# teensy-boom.net
KiCad netlist of a schematic drawn in EAGLE
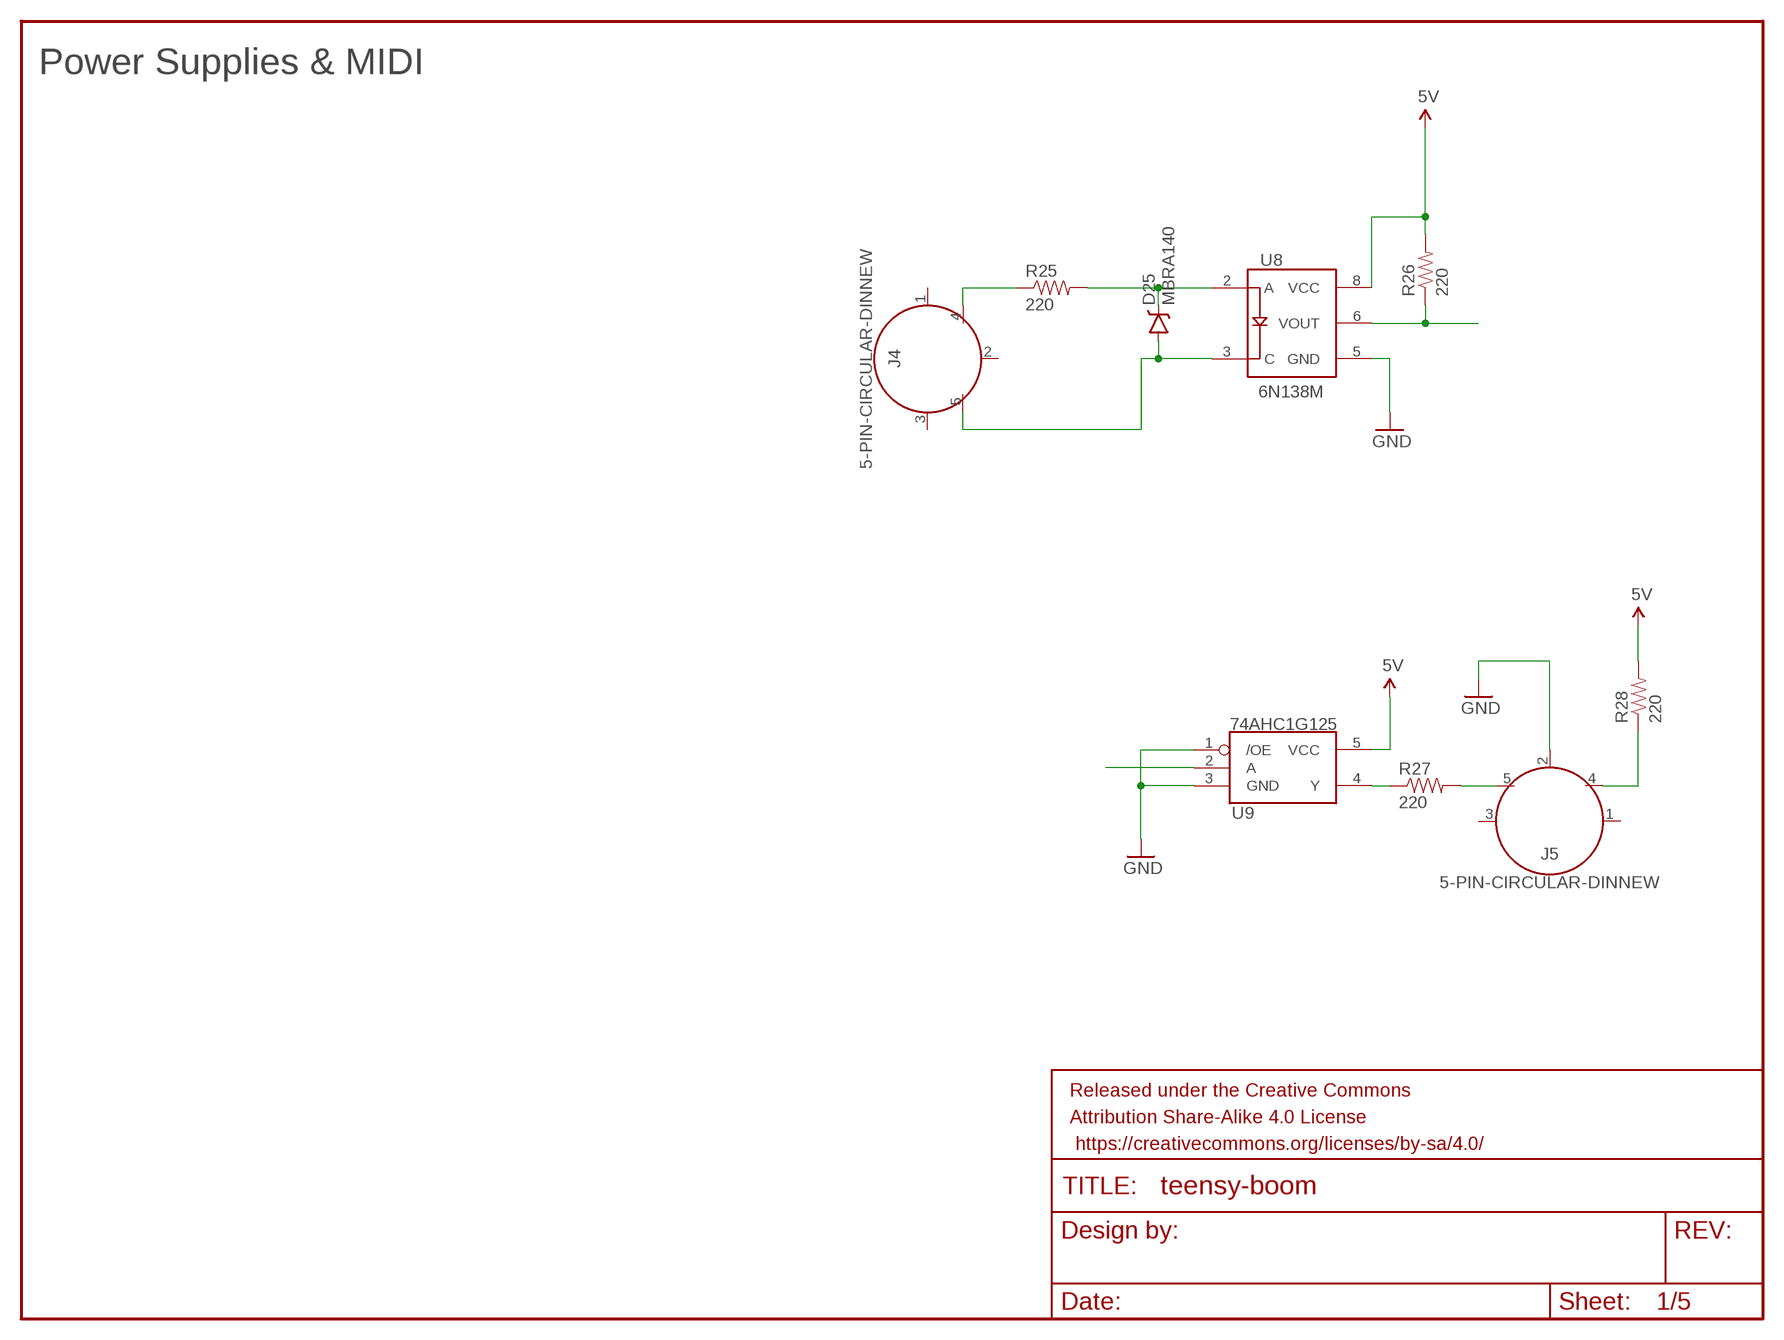
[diagram p0: schematic, sheet 1]
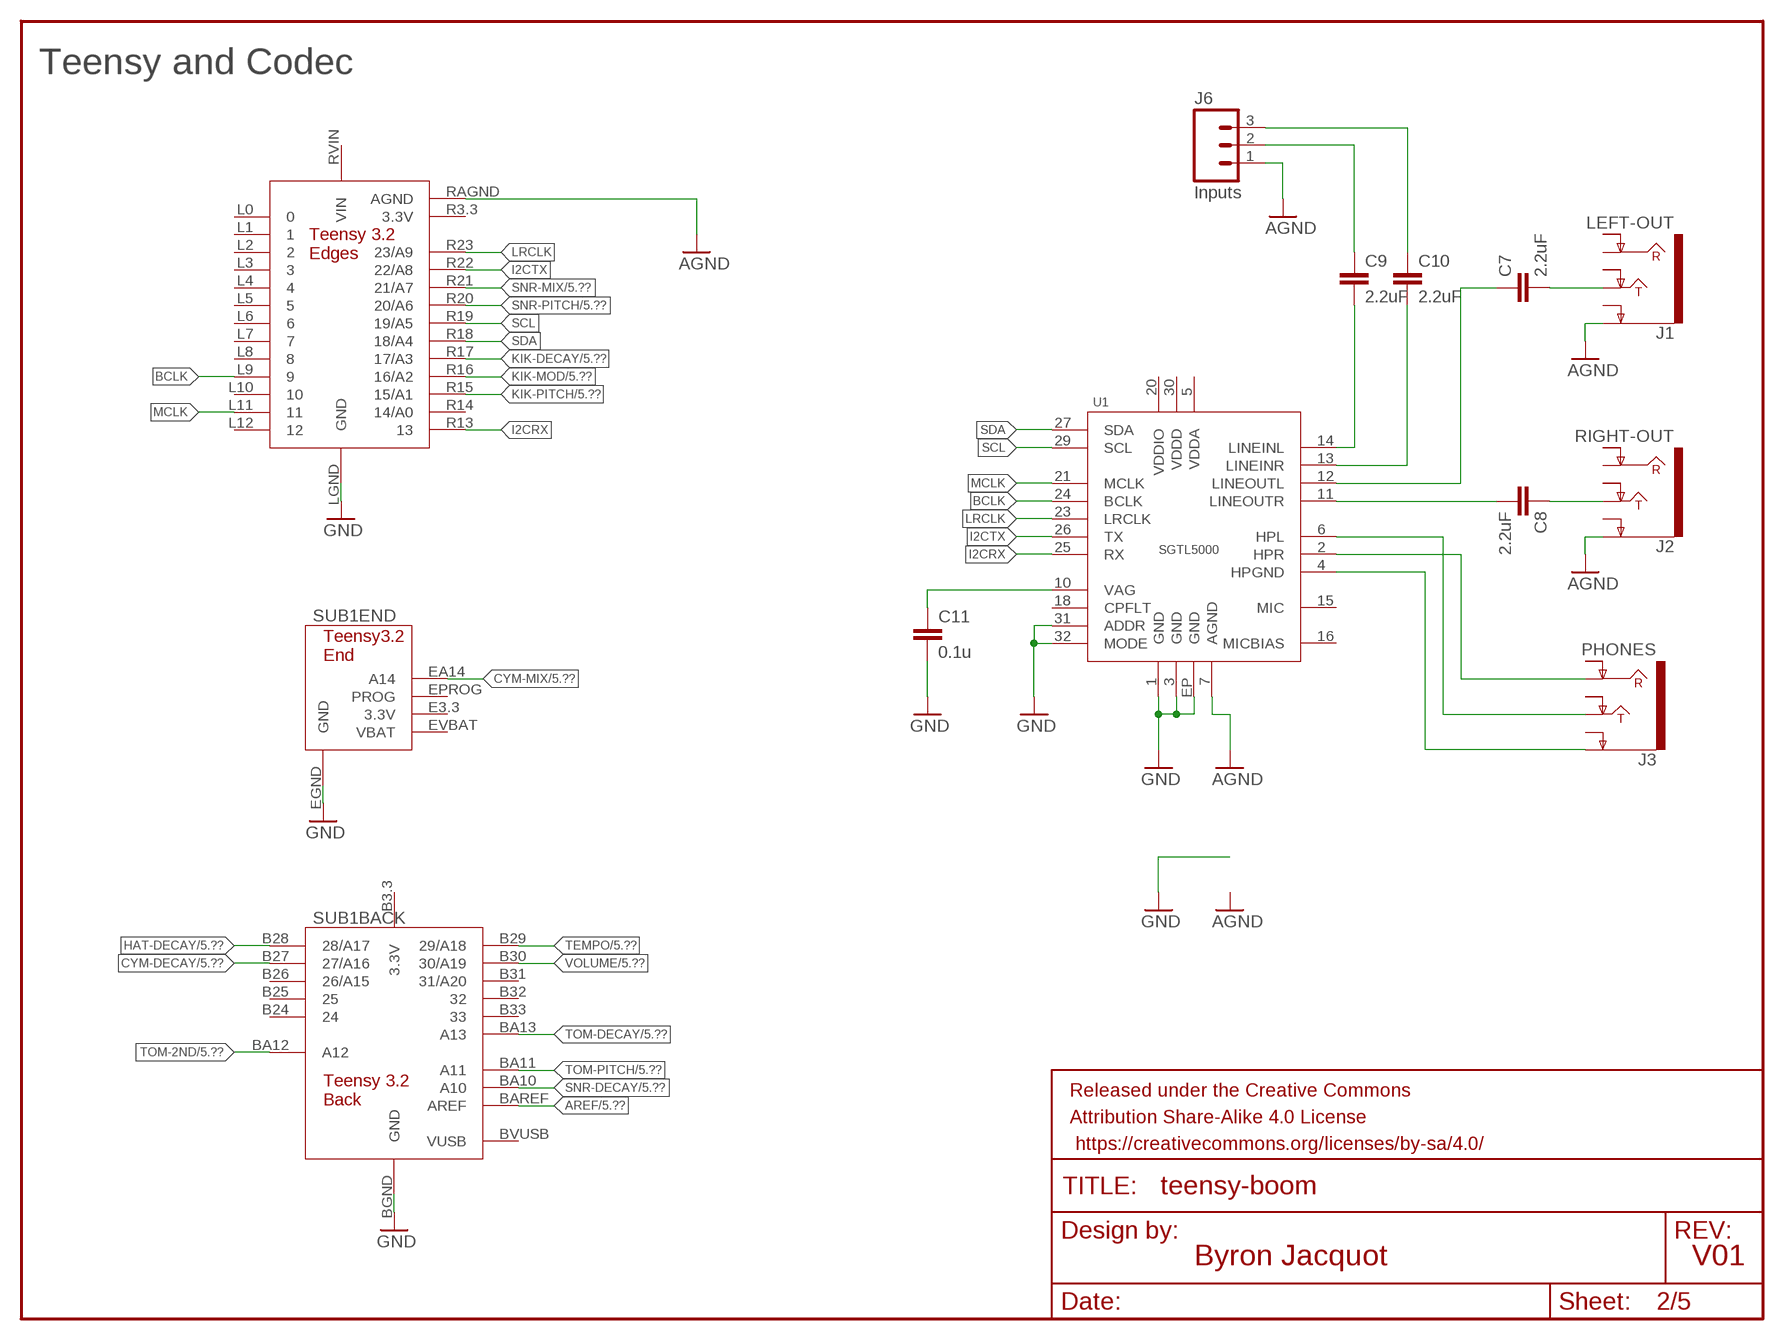
[diagram p1: schematic, sheet 2]
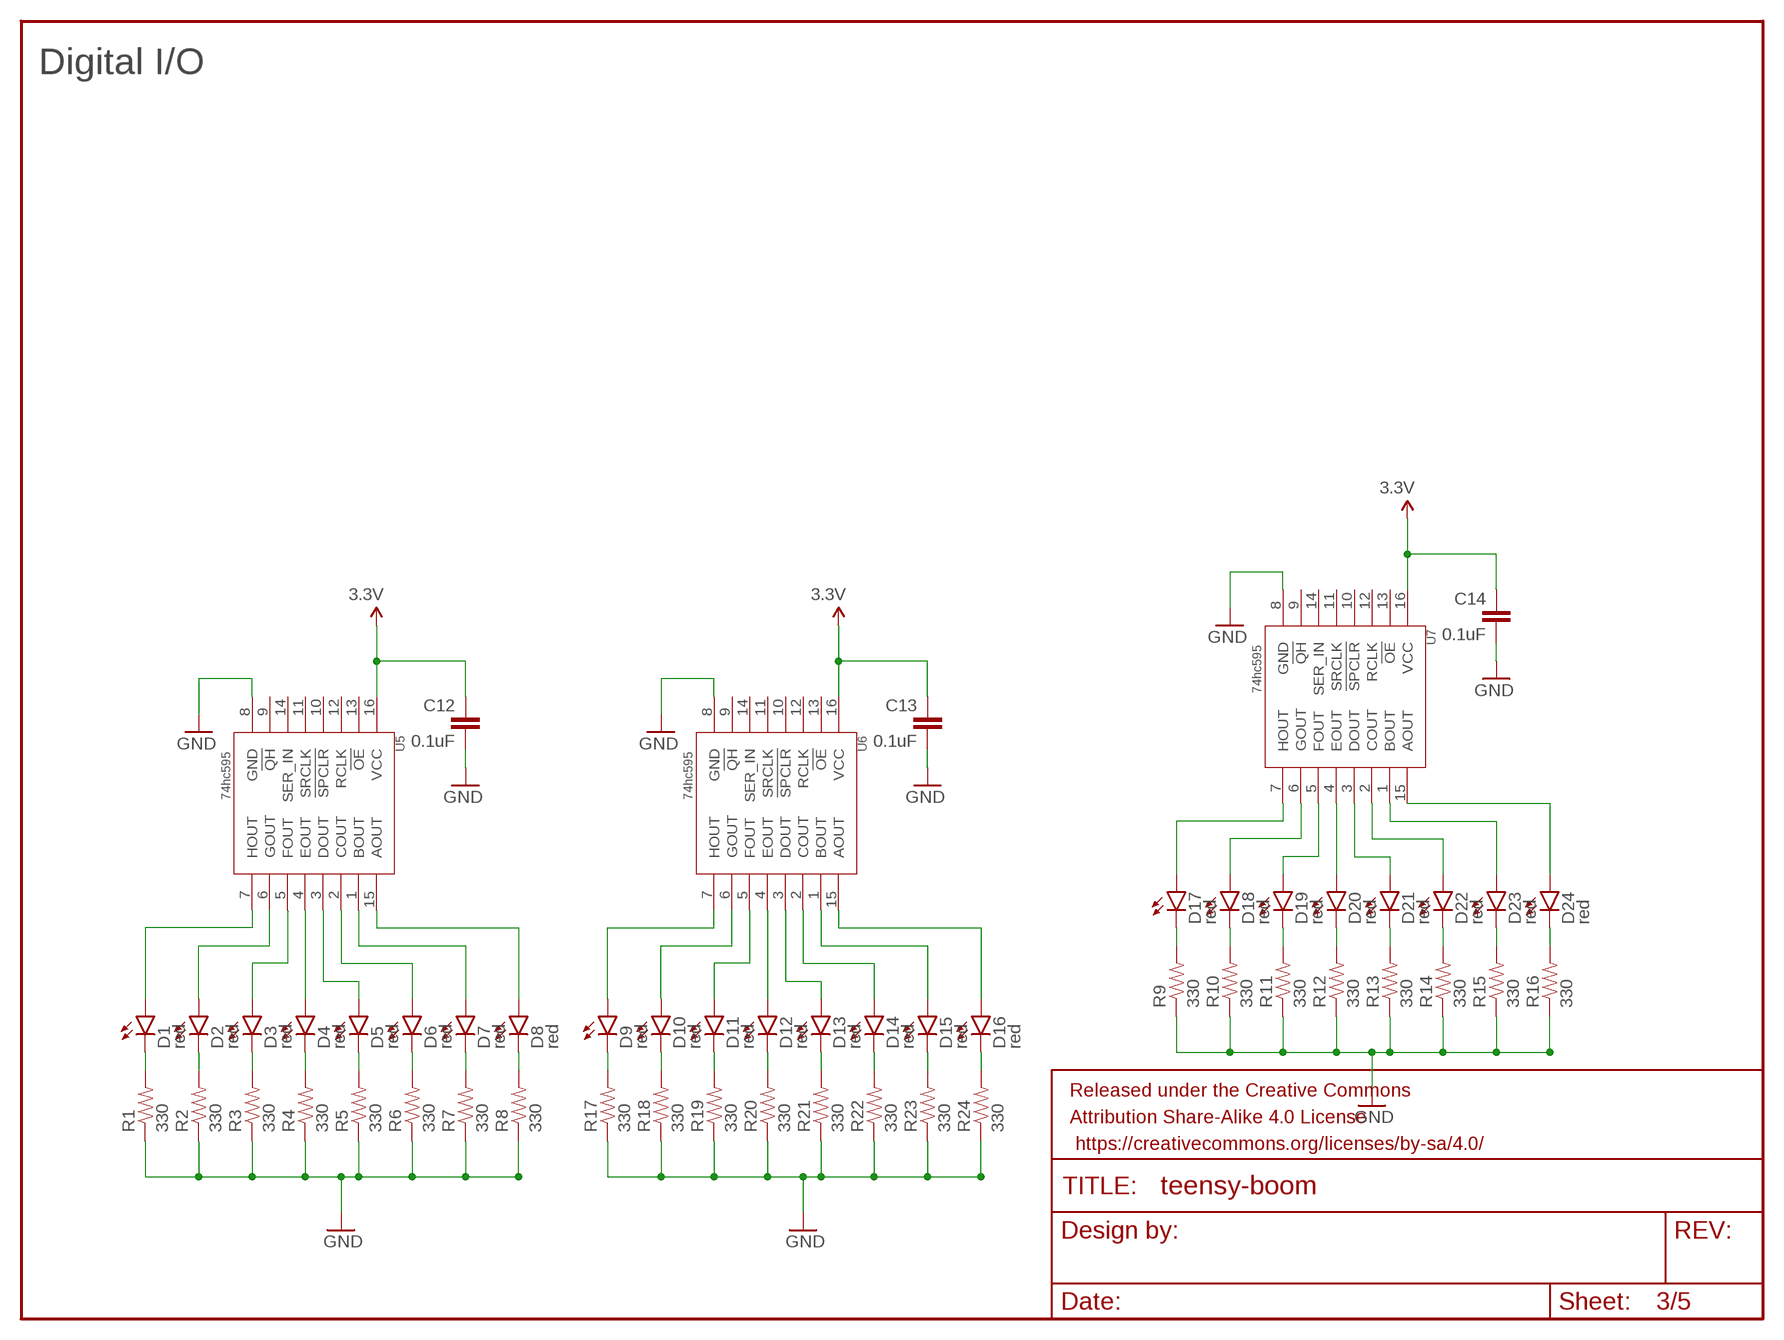
[diagram p2: schematic, sheet 3]
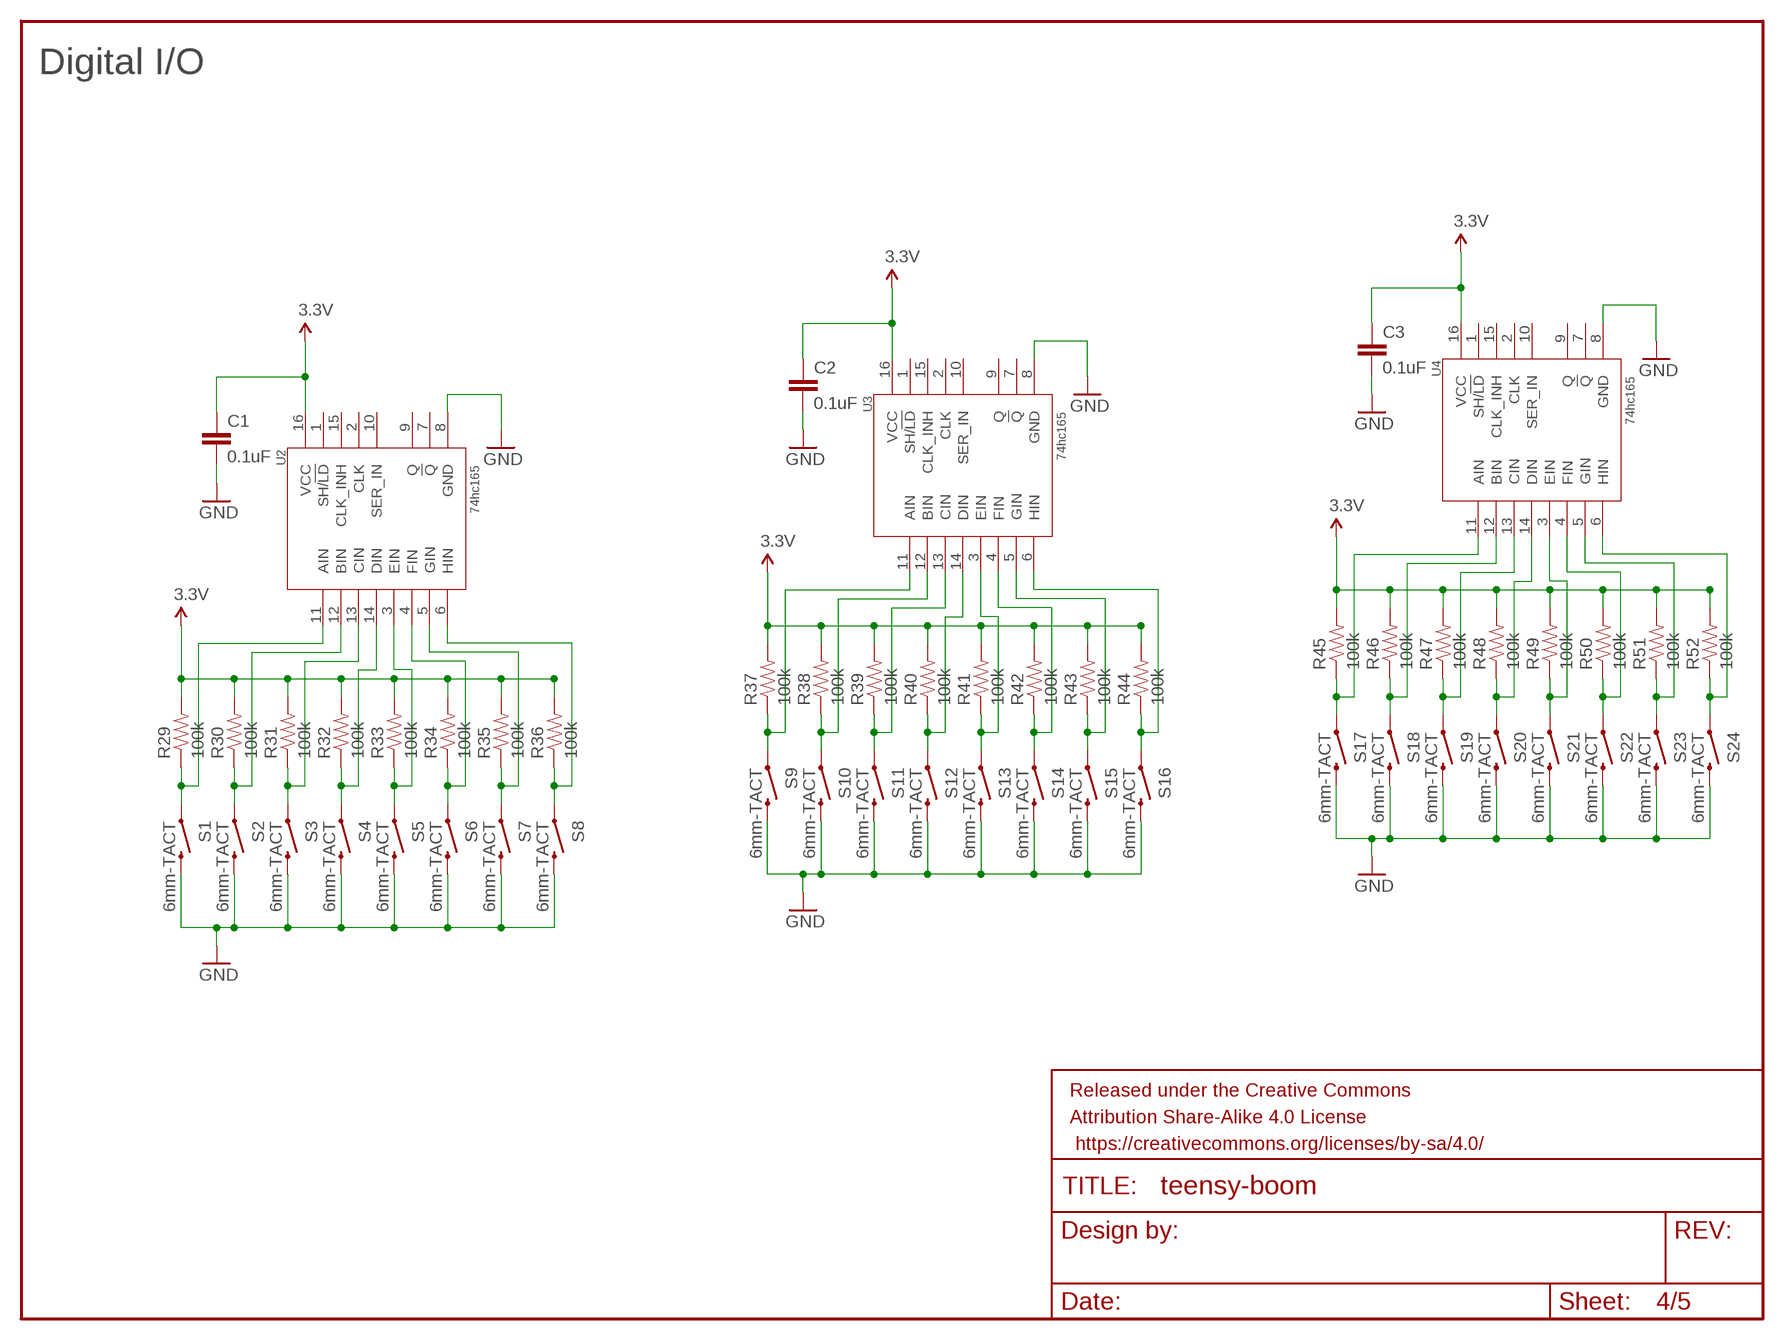
[diagram p3: schematic, sheet 4]
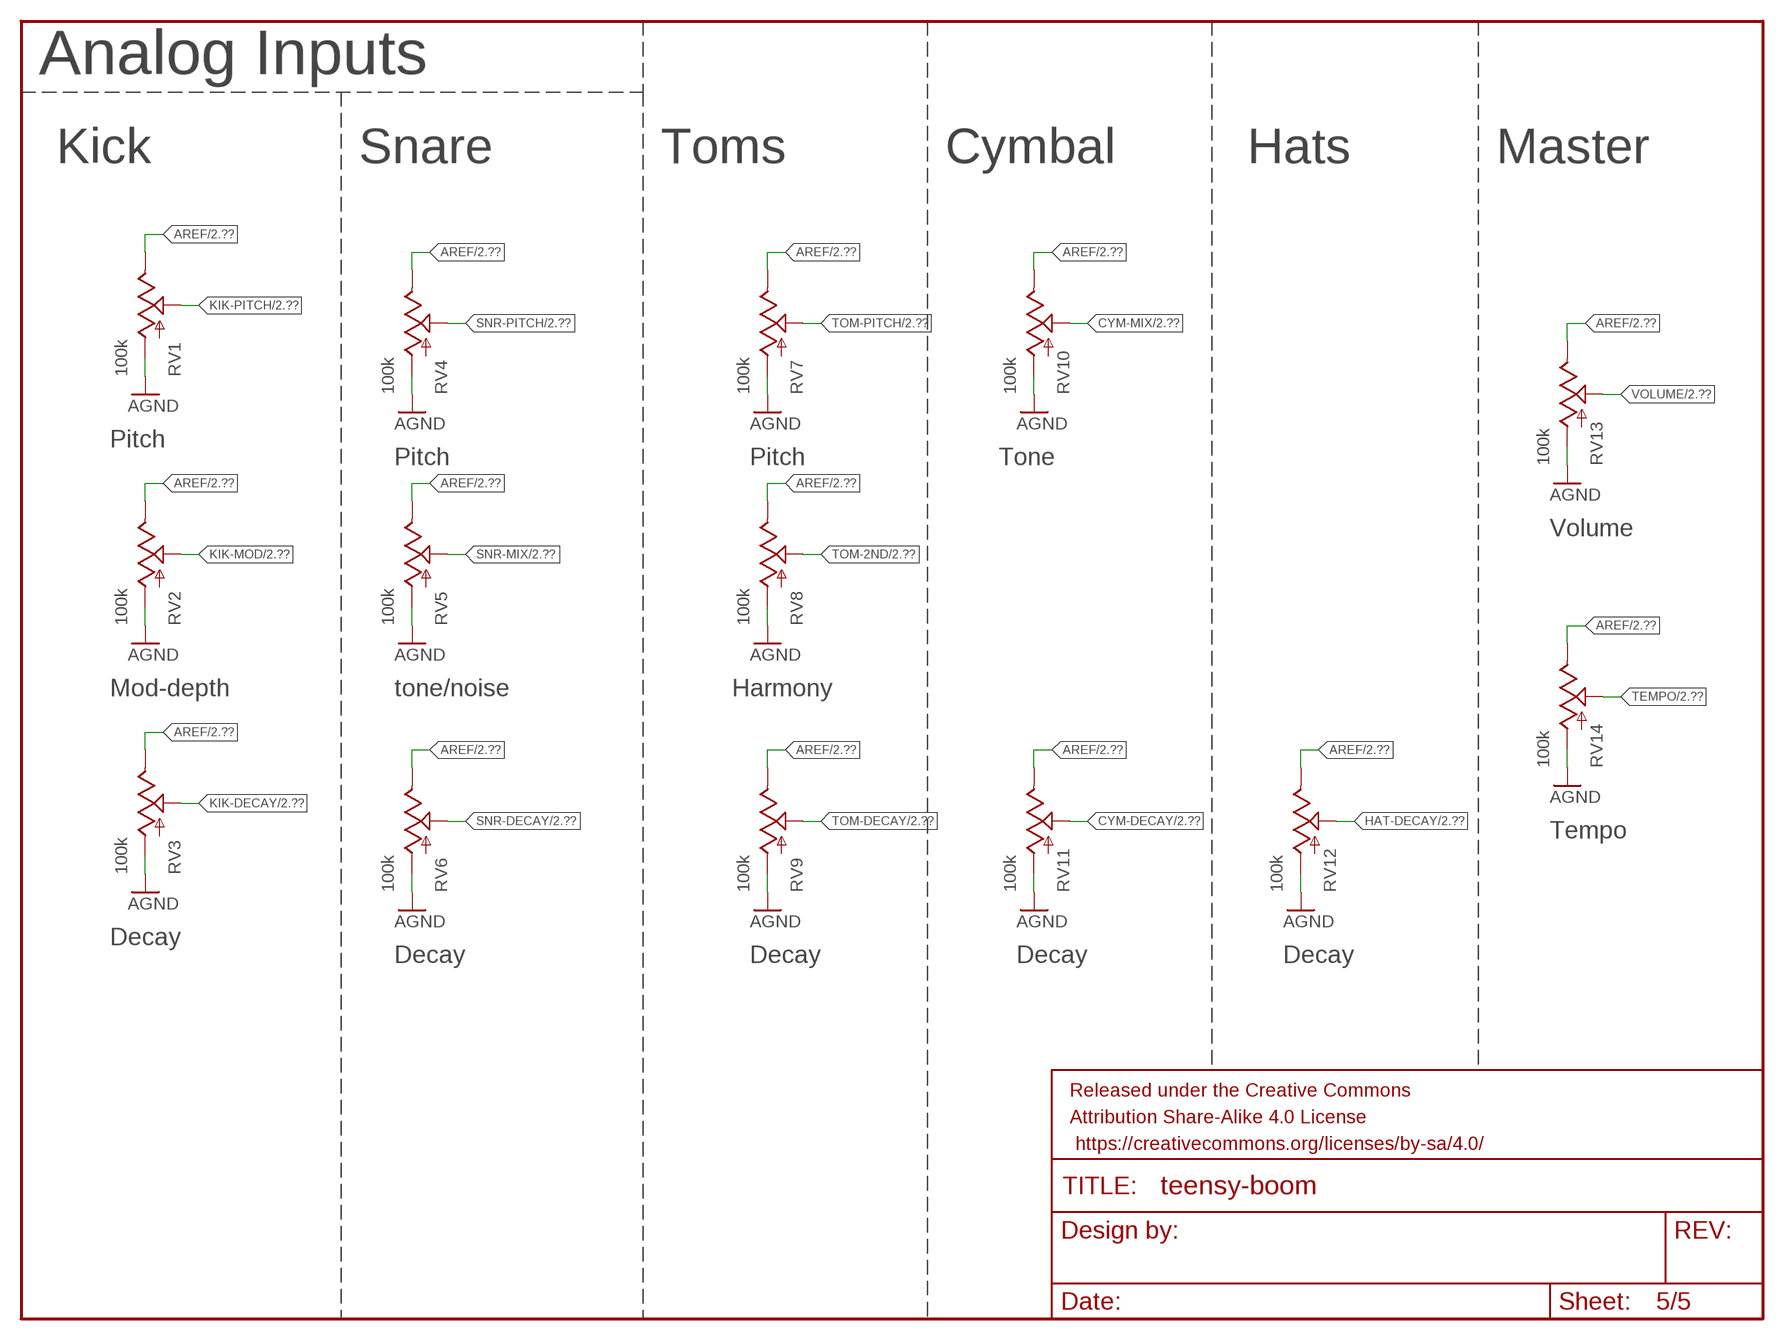
[diagram p4: schematic, sheet 5]

(export (version "E")
  (design (tool "Eeschema 10.0.6"))
  (components
    (comp (ref "C1")
      (value "0.1uF")
      (footprint "eagle-import:0603-CAP")
      (libsource (lib "eagle-import") (part "0.1UF-25V-5%(0603)"))
    )
    (comp (ref "C2")
      (value "0.1uF")
      (footprint "eagle-import:0603-CAP")
      (libsource (lib "eagle-import") (part "0.1UF-25V-5%(0603)"))
    )
    (comp (ref "C3")
      (value "0.1uF")
      (footprint "eagle-import:0603-CAP")
      (libsource (lib "eagle-import") (part "0.1UF-25V-5%(0603)"))
    )
    (comp (ref "FRAME5")
      (value "FRAME-LETTERNO_PACKAGE")
      (footprint "eagle-import:DUMMY")
      (fields (field (name "DESIGNER") "Nobody"))
      (libsource (lib "eagle-import") (part "FRAME-LETTERNO_PACKAGE"))
    )
    (comp (ref "R29")
      (value "100k")
      (footprint "eagle-import:0805")
      (libsource (lib "eagle-import") (part "RESISTOR0805-RES"))
    )
    (comp (ref "R30")
      (value "100k")
      (footprint "eagle-import:0805")
      (libsource (lib "eagle-import") (part "RESISTOR0805-RES"))
    )
    (comp (ref "R31")
      (value "100k")
      (footprint "eagle-import:0805")
      (libsource (lib "eagle-import") (part "RESISTOR0805-RES"))
    )
    (comp (ref "R32")
      (value "100k")
      (footprint "eagle-import:0805")
      (libsource (lib "eagle-import") (part "RESISTOR0805-RES"))
    )
    (comp (ref "R33")
      (value "100k")
      (footprint "eagle-import:0805")
      (libsource (lib "eagle-import") (part "RESISTOR0805-RES"))
    )
    (comp (ref "R34")
      (value "100k")
      (footprint "eagle-import:0805")
      (libsource (lib "eagle-import") (part "RESISTOR0805-RES"))
    )
    (comp (ref "R35")
      (value "100k")
      (footprint "eagle-import:0805")
      (libsource (lib "eagle-import") (part "RESISTOR0805-RES"))
    )
    (comp (ref "R36")
      (value "100k")
      (footprint "eagle-import:0805")
      (libsource (lib "eagle-import") (part "RESISTOR0805-RES"))
    )
    (comp (ref "R37")
      (value "100k")
      (footprint "eagle-import:0805")
      (libsource (lib "eagle-import") (part "RESISTOR0805-RES"))
    )
    (comp (ref "R38")
      (value "100k")
      (footprint "eagle-import:0805")
      (libsource (lib "eagle-import") (part "RESISTOR0805-RES"))
    )
    (comp (ref "R39")
      (value "100k")
      (footprint "eagle-import:0805")
      (libsource (lib "eagle-import") (part "RESISTOR0805-RES"))
    )
    (comp (ref "R40")
      (value "100k")
      (footprint "eagle-import:0805")
      (libsource (lib "eagle-import") (part "RESISTOR0805-RES"))
    )
    (comp (ref "R41")
      (value "100k")
      (footprint "eagle-import:0805")
      (libsource (lib "eagle-import") (part "RESISTOR0805-RES"))
    )
    (comp (ref "R42")
      (value "100k")
      (footprint "eagle-import:0805")
      (libsource (lib "eagle-import") (part "RESISTOR0805-RES"))
    )
    (comp (ref "R43")
      (value "100k")
      (footprint "eagle-import:0805")
      (libsource (lib "eagle-import") (part "RESISTOR0805-RES"))
    )
    (comp (ref "R44")
      (value "100k")
      (footprint "eagle-import:0805")
      (libsource (lib "eagle-import") (part "RESISTOR0805-RES"))
    )
    (comp (ref "R45")
      (value "100k")
      (footprint "eagle-import:0805")
      (libsource (lib "eagle-import") (part "RESISTOR0805-RES"))
    )
    (comp (ref "R46")
      (value "100k")
      (footprint "eagle-import:0805")
      (libsource (lib "eagle-import") (part "RESISTOR0805-RES"))
    )
    (comp (ref "R47")
      (value "100k")
      (footprint "eagle-import:0805")
      (libsource (lib "eagle-import") (part "RESISTOR0805-RES"))
    )
    (comp (ref "R48")
      (value "100k")
      (footprint "eagle-import:0805")
      (libsource (lib "eagle-import") (part "RESISTOR0805-RES"))
    )
    (comp (ref "R49")
      (value "100k")
      (footprint "eagle-import:0805")
      (libsource (lib "eagle-import") (part "RESISTOR0805-RES"))
    )
    (comp (ref "R50")
      (value "100k")
      (footprint "eagle-import:0805")
      (libsource (lib "eagle-import") (part "RESISTOR0805-RES"))
    )
    (comp (ref "R51")
      (value "100k")
      (footprint "eagle-import:0805")
      (libsource (lib "eagle-import") (part "RESISTOR0805-RES"))
    )
    (comp (ref "R52")
      (value "100k")
      (footprint "eagle-import:0805")
      (libsource (lib "eagle-import") (part "RESISTOR0805-RES"))
    )
    (comp (ref "S1")
      (value "6mm-TACT")
      (footprint "eagle-import:TACTILE-PTH")
      (libsource (lib "eagle-import") (part "SWITCH-MOMENTARY-2PTH"))
    )
    (comp (ref "S2")
      (value "6mm-TACT")
      (footprint "eagle-import:TACTILE-PTH")
      (libsource (lib "eagle-import") (part "SWITCH-MOMENTARY-2PTH"))
    )
    (comp (ref "S3")
      (value "6mm-TACT")
      (footprint "eagle-import:TACTILE-PTH")
      (libsource (lib "eagle-import") (part "SWITCH-MOMENTARY-2PTH"))
    )
    (comp (ref "S4")
      (value "6mm-TACT")
      (footprint "eagle-import:TACTILE-PTH")
      (libsource (lib "eagle-import") (part "SWITCH-MOMENTARY-2PTH"))
    )
    (comp (ref "S5")
      (value "6mm-TACT")
      (footprint "eagle-import:TACTILE-PTH")
      (libsource (lib "eagle-import") (part "SWITCH-MOMENTARY-2PTH"))
    )
    (comp (ref "S6")
      (value "6mm-TACT")
      (footprint "eagle-import:TACTILE-PTH")
      (libsource (lib "eagle-import") (part "SWITCH-MOMENTARY-2PTH"))
    )
    (comp (ref "S7")
      (value "6mm-TACT")
      (footprint "eagle-import:TACTILE-PTH")
      (libsource (lib "eagle-import") (part "SWITCH-MOMENTARY-2PTH"))
    )
    (comp (ref "S8")
      (value "6mm-TACT")
      (footprint "eagle-import:TACTILE-PTH")
      (libsource (lib "eagle-import") (part "SWITCH-MOMENTARY-2PTH"))
    )
    (comp (ref "S9")
      (value "6mm-TACT")
      (footprint "eagle-import:TACTILE-PTH")
      (libsource (lib "eagle-import") (part "SWITCH-MOMENTARY-2PTH"))
    )
    (comp (ref "S10")
      (value "6mm-TACT")
      (footprint "eagle-import:TACTILE-PTH")
      (libsource (lib "eagle-import") (part "SWITCH-MOMENTARY-2PTH"))
    )
    (comp (ref "S11")
      (value "6mm-TACT")
      (footprint "eagle-import:TACTILE-PTH")
      (libsource (lib "eagle-import") (part "SWITCH-MOMENTARY-2PTH"))
    )
    (comp (ref "S12")
      (value "6mm-TACT")
      (footprint "eagle-import:TACTILE-PTH")
      (libsource (lib "eagle-import") (part "SWITCH-MOMENTARY-2PTH"))
    )
    (comp (ref "S13")
      (value "6mm-TACT")
      (footprint "eagle-import:TACTILE-PTH")
      (libsource (lib "eagle-import") (part "SWITCH-MOMENTARY-2PTH"))
    )
    (comp (ref "S14")
      (value "6mm-TACT")
      (footprint "eagle-import:TACTILE-PTH")
      (libsource (lib "eagle-import") (part "SWITCH-MOMENTARY-2PTH"))
    )
    (comp (ref "S15")
      (value "6mm-TACT")
      (footprint "eagle-import:TACTILE-PTH")
      (libsource (lib "eagle-import") (part "SWITCH-MOMENTARY-2PTH"))
    )
    (comp (ref "S16")
      (value "6mm-TACT")
      (footprint "eagle-import:TACTILE-PTH")
      (libsource (lib "eagle-import") (part "SWITCH-MOMENTARY-2PTH"))
    )
    (comp (ref "S17")
      (value "6mm-TACT")
      (footprint "eagle-import:TACTILE-PTH")
      (libsource (lib "eagle-import") (part "SWITCH-MOMENTARY-2PTH"))
    )
    (comp (ref "S18")
      (value "6mm-TACT")
      (footprint "eagle-import:TACTILE-PTH")
      (libsource (lib "eagle-import") (part "SWITCH-MOMENTARY-2PTH"))
    )
    (comp (ref "S19")
      (value "6mm-TACT")
      (footprint "eagle-import:TACTILE-PTH")
      (libsource (lib "eagle-import") (part "SWITCH-MOMENTARY-2PTH"))
    )
    (comp (ref "S20")
      (value "6mm-TACT")
      (footprint "eagle-import:TACTILE-PTH")
      (libsource (lib "eagle-import") (part "SWITCH-MOMENTARY-2PTH"))
    )
    (comp (ref "S21")
      (value "6mm-TACT")
      (footprint "eagle-import:TACTILE-PTH")
      (libsource (lib "eagle-import") (part "SWITCH-MOMENTARY-2PTH"))
    )
    (comp (ref "S22")
      (value "6mm-TACT")
      (footprint "eagle-import:TACTILE-PTH")
      (libsource (lib "eagle-import") (part "SWITCH-MOMENTARY-2PTH"))
    )
    (comp (ref "S23")
      (value "6mm-TACT")
      (footprint "eagle-import:TACTILE-PTH")
      (libsource (lib "eagle-import") (part "SWITCH-MOMENTARY-2PTH"))
    )
    (comp (ref "S24")
      (value "6mm-TACT")
      (footprint "eagle-import:TACTILE-PTH")
      (libsource (lib "eagle-import") (part "SWITCH-MOMENTARY-2PTH"))
    )
    (comp (ref "U2")
      (value "74hc165")
      (footprint "eagle-import:SO16")
      (libsource (lib "eagle-import") (part "74HC165"))
    )
    (comp (ref "U3")
      (value "74hc165")
      (footprint "eagle-import:SO16")
      (libsource (lib "eagle-import") (part "74HC165"))
    )
    (comp (ref "U4")
      (value "74hc165")
      (footprint "eagle-import:SO16")
      (libsource (lib "eagle-import") (part "74HC165"))
    )
    (comp (ref "C7")
      (value "2.2uF")
      (footprint "eagle-import:0805-CAP")
      (libsource (lib "eagle-import") (part "2.2UF-25V-+80/-20(0805)"))
    )
    (comp (ref "C8")
      (value "2.2uF")
      (footprint "eagle-import:0805-CAP")
      (libsource (lib "eagle-import") (part "2.2UF-25V-+80/-20(0805)"))
    )
    (comp (ref "C9")
      (value "2.2uF")
      (footprint "eagle-import:0805-CAP")
      (libsource (lib "eagle-import") (part "2.2UF-25V-+80/-20(0805)"))
    )
    (comp (ref "C10")
      (value "2.2uF")
      (footprint "eagle-import:0805-CAP")
      (libsource (lib "eagle-import") (part "2.2UF-25V-+80/-20(0805)"))
    )
    (comp (ref "C11")
      (value "0.1u")
      (footprint "eagle-import:0805")
      (libsource (lib "eagle-import") (part "CAP0805"))
    )
    (comp (ref "FRAME1")
      (value "FRAME-LETTER")
      (footprint "eagle-import:CREATIVE_COMMONS")
      (libsource (lib "eagle-import") (part "FRAME-LETTER"))
    )
    (comp (ref "J1")
      (value "LEFT-OUT")
      (footprint "eagle-import:AUDIO-JACK-.25-INCH-HORIZ-PTH")
      (libsource (lib "eagle-import") (part "AUDIO-JACK4-.25-HORIZ-TRS"))
    )
    (comp (ref "J2")
      (value "RIGHT-OUT")
      (footprint "eagle-import:AUDIO-JACK-.25-INCH-HORIZ-PTH")
      (libsource (lib "eagle-import") (part "AUDIO-JACK4-.25-HORIZ-TRS"))
    )
    (comp (ref "J3")
      (value "PHONES")
      (footprint "eagle-import:AUDIO-JACK-.25-INCH-HORIZ-PTH")
      (libsource (lib "eagle-import") (part "AUDIO-JACK4-.25-HORIZ-TRS"))
    )
    (comp (ref "J6")
      (value "Inputs")
      (footprint "eagle-import:1X03_LOCK")
      (libsource (lib "eagle-import") (part "M03LOCK"))
    )
    (comp (ref "SUB1")
      (value "TEENSY-3.2PTH")
      (footprint "eagle-import:TEENSY-3.2")
      (libsource (lib "eagle-import") (part "TEENSY-3.2PTH"))
    )
    (comp (ref "U1")
      (value "SGTL5000")
      (footprint "eagle-import:QFN-32")
      (libsource (lib "eagle-import") (part "SGTL5000QFN-32"))
    )
    (comp (ref "FRAME4")
      (value "FRAME-LETTERNO_PACKAGE")
      (footprint "eagle-import:DUMMY")
      (fields (field (name "DESIGNER") "Nobody"))
      (libsource (lib "eagle-import") (part "FRAME-LETTERNO_PACKAGE"))
    )
    (comp (ref "RV1")
      (value "100k")
      (footprint "eagle-import:ALPS_POT_KIT")
      (libsource (lib "eagle-import") (part "POTALPS-KIT"))
    )
    (comp (ref "RV2")
      (value "100k")
      (footprint "eagle-import:ALPS_POT_KIT")
      (libsource (lib "eagle-import") (part "POTALPS-KIT"))
    )
    (comp (ref "RV3")
      (value "100k")
      (footprint "eagle-import:ALPS_POT_KIT")
      (libsource (lib "eagle-import") (part "POTALPS-KIT"))
    )
    (comp (ref "RV4")
      (value "100k")
      (footprint "eagle-import:ALPS_POT_KIT")
      (libsource (lib "eagle-import") (part "POTALPS-KIT"))
    )
    (comp (ref "RV5")
      (value "100k")
      (footprint "eagle-import:ALPS_POT_KIT")
      (libsource (lib "eagle-import") (part "POTALPS-KIT"))
    )
    (comp (ref "RV6")
      (value "100k")
      (footprint "eagle-import:ALPS_POT_KIT")
      (libsource (lib "eagle-import") (part "POTALPS-KIT"))
    )
    (comp (ref "RV7")
      (value "100k")
      (footprint "eagle-import:ALPS_POT_KIT")
      (libsource (lib "eagle-import") (part "POTALPS-KIT"))
    )
    (comp (ref "RV8")
      (value "100k")
      (footprint "eagle-import:ALPS_POT_KIT")
      (libsource (lib "eagle-import") (part "POTALPS-KIT"))
    )
    (comp (ref "RV9")
      (value "100k")
      (footprint "eagle-import:ALPS_POT_KIT")
      (libsource (lib "eagle-import") (part "POTALPS-KIT"))
    )
    (comp (ref "RV10")
      (value "100k")
      (footprint "eagle-import:ALPS_POT_KIT")
      (libsource (lib "eagle-import") (part "POTALPS-KIT"))
    )
    (comp (ref "RV11")
      (value "100k")
      (footprint "eagle-import:ALPS_POT_KIT")
      (libsource (lib "eagle-import") (part "POTALPS-KIT"))
    )
    (comp (ref "RV12")
      (value "100k")
      (footprint "eagle-import:ALPS_POT_KIT")
      (libsource (lib "eagle-import") (part "POTALPS-KIT"))
    )
    (comp (ref "RV13")
      (value "100k")
      (footprint "eagle-import:ALPS_POT_KIT")
      (libsource (lib "eagle-import") (part "POTALPS-KIT"))
    )
    (comp (ref "RV14")
      (value "100k")
      (footprint "eagle-import:ALPS_POT_KIT")
      (libsource (lib "eagle-import") (part "POTALPS-KIT"))
    )
    (comp (ref "C12")
      (value "0.1uF")
      (footprint "eagle-import:0603-CAP")
      (libsource (lib "eagle-import") (part "0.1UF-25V-5%(0603)"))
    )
    (comp (ref "C13")
      (value "0.1uF")
      (footprint "eagle-import:0603-CAP")
      (libsource (lib "eagle-import") (part "0.1UF-25V-5%(0603)"))
    )
    (comp (ref "C14")
      (value "0.1uF")
      (footprint "eagle-import:0603-CAP")
      (libsource (lib "eagle-import") (part "0.1UF-25V-5%(0603)"))
    )
    (comp (ref "D1")
      (value "red")
      (footprint "eagle-import:LED3MM-NS")
      (libsource (lib "eagle-import") (part "LED-3MM-NO_SILK"))
    )
    (comp (ref "D2")
      (value "red")
      (footprint "eagle-import:LED3MM-NS")
      (libsource (lib "eagle-import") (part "LED-3MM-NO_SILK"))
    )
    (comp (ref "D3")
      (value "red")
      (footprint "eagle-import:LED3MM-NS")
      (libsource (lib "eagle-import") (part "LED-3MM-NO_SILK"))
    )
    (comp (ref "D4")
      (value "red")
      (footprint "eagle-import:LED3MM-NS")
      (libsource (lib "eagle-import") (part "LED-3MM-NO_SILK"))
    )
    (comp (ref "D5")
      (value "red")
      (footprint "eagle-import:LED3MM-NS")
      (libsource (lib "eagle-import") (part "LED-3MM-NO_SILK"))
    )
    (comp (ref "D6")
      (value "red")
      (footprint "eagle-import:LED3MM-NS")
      (libsource (lib "eagle-import") (part "LED-3MM-NO_SILK"))
    )
    (comp (ref "D7")
      (value "red")
      (footprint "eagle-import:LED3MM-NS")
      (libsource (lib "eagle-import") (part "LED-3MM-NO_SILK"))
    )
    (comp (ref "D8")
      (value "red")
      (footprint "eagle-import:LED3MM-NS")
      (libsource (lib "eagle-import") (part "LED-3MM-NO_SILK"))
    )
    (comp (ref "D9")
      (value "red")
      (footprint "eagle-import:LED3MM-NS")
      (libsource (lib "eagle-import") (part "LED-3MM-NO_SILK"))
    )
    (comp (ref "D10")
      (value "red")
      (footprint "eagle-import:LED3MM-NS")
      (libsource (lib "eagle-import") (part "LED-3MM-NO_SILK"))
    )
    (comp (ref "D11")
      (value "red")
      (footprint "eagle-import:LED3MM-NS")
      (libsource (lib "eagle-import") (part "LED-3MM-NO_SILK"))
    )
    (comp (ref "D12")
      (value "red")
      (footprint "eagle-import:LED3MM-NS")
      (libsource (lib "eagle-import") (part "LED-3MM-NO_SILK"))
    )
    (comp (ref "D13")
      (value "red")
      (footprint "eagle-import:LED3MM-NS")
      (libsource (lib "eagle-import") (part "LED-3MM-NO_SILK"))
    )
    (comp (ref "D14")
      (value "red")
      (footprint "eagle-import:LED3MM-NS")
      (libsource (lib "eagle-import") (part "LED-3MM-NO_SILK"))
    )
    (comp (ref "D15")
      (value "red")
      (footprint "eagle-import:LED3MM-NS")
      (libsource (lib "eagle-import") (part "LED-3MM-NO_SILK"))
    )
    (comp (ref "D16")
      (value "red")
      (footprint "eagle-import:LED3MM-NS")
      (libsource (lib "eagle-import") (part "LED-3MM-NO_SILK"))
    )
    (comp (ref "D17")
      (value "red")
      (footprint "eagle-import:LED3MM-NS")
      (libsource (lib "eagle-import") (part "LED-3MM-NO_SILK"))
    )
    (comp (ref "D18")
      (value "red")
      (footprint "eagle-import:LED3MM-NS")
      (libsource (lib "eagle-import") (part "LED-3MM-NO_SILK"))
    )
    (comp (ref "D19")
      (value "red")
      (footprint "eagle-import:LED3MM-NS")
      (libsource (lib "eagle-import") (part "LED-3MM-NO_SILK"))
    )
    (comp (ref "D20")
      (value "red")
      (footprint "eagle-import:LED3MM-NS")
      (libsource (lib "eagle-import") (part "LED-3MM-NO_SILK"))
    )
    (comp (ref "D21")
      (value "red")
      (footprint "eagle-import:LED3MM-NS")
      (libsource (lib "eagle-import") (part "LED-3MM-NO_SILK"))
    )
    (comp (ref "D22")
      (value "red")
      (footprint "eagle-import:LED3MM-NS")
      (libsource (lib "eagle-import") (part "LED-3MM-NO_SILK"))
    )
    (comp (ref "D23")
      (value "red")
      (footprint "eagle-import:LED3MM-NS")
      (libsource (lib "eagle-import") (part "LED-3MM-NO_SILK"))
    )
    (comp (ref "D24")
      (value "red")
      (footprint "eagle-import:LED3MM-NS")
      (libsource (lib "eagle-import") (part "LED-3MM-NO_SILK"))
    )
    (comp (ref "FRAME3")
      (value "FRAME-LETTERNO_PACKAGE")
      (footprint "eagle-import:DUMMY")
      (fields (field (name "DESIGNER") "Nobody"))
      (libsource (lib "eagle-import") (part "FRAME-LETTERNO_PACKAGE"))
    )
    (comp (ref "R1")
      (value "330")
      (footprint "eagle-import:0603-RES")
      (libsource (lib "eagle-import") (part "330OHM1/10W1%(0603)"))
    )
    (comp (ref "R2")
      (value "330")
      (footprint "eagle-import:0603-RES")
      (libsource (lib "eagle-import") (part "330OHM1/10W1%(0603)"))
    )
    (comp (ref "R3")
      (value "330")
      (footprint "eagle-import:0603-RES")
      (libsource (lib "eagle-import") (part "330OHM1/10W1%(0603)"))
    )
    (comp (ref "R4")
      (value "330")
      (footprint "eagle-import:0603-RES")
      (libsource (lib "eagle-import") (part "330OHM1/10W1%(0603)"))
    )
    (comp (ref "R5")
      (value "330")
      (footprint "eagle-import:0603-RES")
      (libsource (lib "eagle-import") (part "330OHM1/10W1%(0603)"))
    )
    (comp (ref "R6")
      (value "330")
      (footprint "eagle-import:0603-RES")
      (libsource (lib "eagle-import") (part "330OHM1/10W1%(0603)"))
    )
    (comp (ref "R7")
      (value "330")
      (footprint "eagle-import:0603-RES")
      (libsource (lib "eagle-import") (part "330OHM1/10W1%(0603)"))
    )
    (comp (ref "R8")
      (value "330")
      (footprint "eagle-import:0603-RES")
      (libsource (lib "eagle-import") (part "330OHM1/10W1%(0603)"))
    )
    (comp (ref "R9")
      (value "330")
      (footprint "eagle-import:0603-RES")
      (libsource (lib "eagle-import") (part "330OHM1/10W1%(0603)"))
    )
    (comp (ref "R10")
      (value "330")
      (footprint "eagle-import:0603-RES")
      (libsource (lib "eagle-import") (part "330OHM1/10W1%(0603)"))
    )
    (comp (ref "R11")
      (value "330")
      (footprint "eagle-import:0603-RES")
      (libsource (lib "eagle-import") (part "330OHM1/10W1%(0603)"))
    )
    (comp (ref "R12")
      (value "330")
      (footprint "eagle-import:0603-RES")
      (libsource (lib "eagle-import") (part "330OHM1/10W1%(0603)"))
    )
    (comp (ref "R13")
      (value "330")
      (footprint "eagle-import:0603-RES")
      (libsource (lib "eagle-import") (part "330OHM1/10W1%(0603)"))
    )
    (comp (ref "R14")
      (value "330")
      (footprint "eagle-import:0603-RES")
      (libsource (lib "eagle-import") (part "330OHM1/10W1%(0603)"))
    )
    (comp (ref "R15")
      (value "330")
      (footprint "eagle-import:0603-RES")
      (libsource (lib "eagle-import") (part "330OHM1/10W1%(0603)"))
    )
    (comp (ref "R16")
      (value "330")
      (footprint "eagle-import:0603-RES")
      (libsource (lib "eagle-import") (part "330OHM1/10W1%(0603)"))
    )
    (comp (ref "R17")
      (value "330")
      (footprint "eagle-import:0603-RES")
      (libsource (lib "eagle-import") (part "330OHM1/10W1%(0603)"))
    )
    (comp (ref "R18")
      (value "330")
      (footprint "eagle-import:0603-RES")
      (libsource (lib "eagle-import") (part "330OHM1/10W1%(0603)"))
    )
    (comp (ref "R19")
      (value "330")
      (footprint "eagle-import:0603-RES")
      (libsource (lib "eagle-import") (part "330OHM1/10W1%(0603)"))
    )
    (comp (ref "R20")
      (value "330")
      (footprint "eagle-import:0603-RES")
      (libsource (lib "eagle-import") (part "330OHM1/10W1%(0603)"))
    )
    (comp (ref "R21")
      (value "330")
      (footprint "eagle-import:0603-RES")
      (libsource (lib "eagle-import") (part "330OHM1/10W1%(0603)"))
    )
    (comp (ref "R22")
      (value "330")
      (footprint "eagle-import:0603-RES")
      (libsource (lib "eagle-import") (part "330OHM1/10W1%(0603)"))
    )
    (comp (ref "R23")
      (value "330")
      (footprint "eagle-import:0603-RES")
      (libsource (lib "eagle-import") (part "330OHM1/10W1%(0603)"))
    )
    (comp (ref "R24")
      (value "330")
      (footprint "eagle-import:0603-RES")
      (libsource (lib "eagle-import") (part "330OHM1/10W1%(0603)"))
    )
    (comp (ref "U5")
      (value "74hc595")
      (footprint "eagle-import:SO16")
      (libsource (lib "eagle-import") (part "74HC595"))
    )
    (comp (ref "U6")
      (value "74hc595")
      (footprint "eagle-import:SO16")
      (libsource (lib "eagle-import") (part "74HC595"))
    )
    (comp (ref "U7")
      (value "74hc595")
      (footprint "eagle-import:SO16")
      (libsource (lib "eagle-import") (part "74HC595"))
    )
    (comp (ref "D25")
      (value "MBRA140")
      (footprint "eagle-import:SMA-DIODE")
      (libsource (lib "eagle-import") (part "DIODE-SCHOTTKY-MBRA140"))
    )
    (comp (ref "FRAME2")
      (value "FRAME-LETTERNO_PACKAGE")
      (footprint "eagle-import:DUMMY")
      (fields (field (name "DESIGNER") "Nobody"))
      (libsource (lib "eagle-import") (part "FRAME-LETTERNO_PACKAGE"))
    )
    (comp (ref "J4")
      (value "5-PIN-CIRCULAR-DINNEW")
      (footprint "eagle-import:5-PIN-DIN-RA-PCB-NEW")
      (libsource (lib "eagle-import") (part "5-PIN-CIRCULAR-DINNEW"))
    )
    (comp (ref "J5")
      (value "5-PIN-CIRCULAR-DINNEW")
      (footprint "eagle-import:5-PIN-DIN-RA-PCB-NEW")
      (libsource (lib "eagle-import") (part "5-PIN-CIRCULAR-DINNEW"))
    )
    (comp (ref "R25")
      (value "220")
      (footprint "eagle-import:0603-RES")
      (libsource (lib "eagle-import") (part "220OHM-1/10W-1%(0603)"))
    )
    (comp (ref "R26")
      (value "220")
      (footprint "eagle-import:0603-RES")
      (libsource (lib "eagle-import") (part "220OHM-1/10W-1%(0603)"))
    )
    (comp (ref "R27")
      (value "220")
      (footprint "eagle-import:0603-RES")
      (libsource (lib "eagle-import") (part "220OHM-1/10W-1%(0603)"))
    )
    (comp (ref "R28")
      (value "220")
      (footprint "eagle-import:0603-RES")
      (libsource (lib "eagle-import") (part "220OHM-1/10W-1%(0603)"))
    )
    (comp (ref "U8")
      (value "6N138M")
      (footprint "eagle-import:8-SMD")
      (libsource (lib "eagle-import") (part "OPTO_DARL_6N138S"))
    )
    (comp (ref "U9")
      (value "74AHC1G125")
      (footprint "eagle-import:SOT23-5")
      (libsource (lib "eagle-import") (part "74AHC1G125"))
    )
  )
  (nets
    (net (code "1") (name "3.3V") (class "Default")
      (node (ref "C1") (pin "1") (pinfunction "1_1") (pintype "passive"))
      (node (ref "C12") (pin "1") (pinfunction "1_1") (pintype "passive"))
      (node (ref "C13") (pin "1") (pinfunction "1_1") (pintype "passive"))
      (node (ref "C14") (pin "1") (pinfunction "1_1") (pintype "passive"))
      (node (ref "C2") (pin "1") (pinfunction "1_1") (pintype "passive"))
      (node (ref "C3") (pin "1") (pinfunction "1_1") (pintype "passive"))
      (node (ref "R29") (pin "2") (pinfunction "2_2") (pintype "passive"))
      (node (ref "R30") (pin "2") (pinfunction "2_2") (pintype "passive"))
      (node (ref "R31") (pin "2") (pinfunction "2_2") (pintype "passive"))
      (node (ref "R32") (pin "2") (pinfunction "2_2") (pintype "passive"))
      (node (ref "R33") (pin "2") (pinfunction "2_2") (pintype "passive"))
      (node (ref "R34") (pin "2") (pinfunction "2_2") (pintype "passive"))
      (node (ref "R35") (pin "2") (pinfunction "2_2") (pintype "passive"))
      (node (ref "R36") (pin "2") (pinfunction "2_2") (pintype "passive"))
      (node (ref "R37") (pin "2") (pinfunction "2_2") (pintype "passive"))
      (node (ref "R38") (pin "2") (pinfunction "2_2") (pintype "passive"))
      (node (ref "R39") (pin "2") (pinfunction "2_2") (pintype "passive"))
      (node (ref "R40") (pin "2") (pinfunction "2_2") (pintype "passive"))
      (node (ref "R41") (pin "2") (pinfunction "2_2") (pintype "passive"))
      (node (ref "R42") (pin "2") (pinfunction "2_2") (pintype "passive"))
      (node (ref "R43") (pin "2") (pinfunction "2_2") (pintype "passive"))
      (node (ref "R44") (pin "2") (pinfunction "2_2") (pintype "passive"))
      (node (ref "R45") (pin "2") (pinfunction "2_2") (pintype "passive"))
      (node (ref "R46") (pin "2") (pinfunction "2_2") (pintype "passive"))
      (node (ref "R47") (pin "2") (pinfunction "2_2") (pintype "passive"))
      (node (ref "R48") (pin "2") (pinfunction "2_2") (pintype "passive"))
      (node (ref "R49") (pin "2") (pinfunction "2_2") (pintype "passive"))
      (node (ref "R50") (pin "2") (pinfunction "2_2") (pintype "passive"))
      (node (ref "R51") (pin "2") (pinfunction "2_2") (pintype "passive"))
      (node (ref "R52") (pin "2") (pinfunction "2_2") (pintype "passive"))
      (node (ref "U2") (pin "16") (pinfunction "VCC_16") (pintype "bidirectional"))
      (node (ref "U3") (pin "16") (pinfunction "VCC_16") (pintype "bidirectional"))
      (node (ref "U4") (pin "16") (pinfunction "VCC_16") (pintype "bidirectional"))
      (node (ref "U5") (pin "16") (pinfunction "VCC_16") (pintype "bidirectional"))
      (node (ref "U6") (pin "16") (pinfunction "VCC_16") (pintype "bidirectional"))
      (node (ref "U7") (pin "16") (pinfunction "VCC_16") (pintype "bidirectional"))
    )
    (net (code "2") (name "5V") (class "Default")
      (node (ref "R26") (pin "2") (pinfunction "2_2") (pintype "passive"))
      (node (ref "R28") (pin "2") (pinfunction "2_2") (pintype "passive"))
      (node (ref "U8") (pin "8") (pinfunction "VCC_8") (pintype "bidirectional"))
      (node (ref "U9") (pin "5") (pinfunction "VCC_5") (pintype "bidirectional"))
    )
    (net (code "3") (name "AGND") (class "Default")
      (node (ref "J1") (pin "SLEEVE") (pinfunction "EARTH_SLEEVE") (pintype "bidirectional"))
      (node (ref "J2") (pin "SLEEVE") (pinfunction "EARTH_SLEEVE") (pintype "bidirectional"))
      (node (ref "J6") (pin "1") (pinfunction "1_1") (pintype "passive"))
      (node (ref "RV1") (pin "P$3") (pinfunction "A_P$3") (pintype "passive"))
      (node (ref "RV10") (pin "P$3") (pinfunction "A_P$3") (pintype "passive"))
      (node (ref "RV11") (pin "P$3") (pinfunction "A_P$3") (pintype "passive"))
      (node (ref "RV12") (pin "P$3") (pinfunction "A_P$3") (pintype "passive"))
      (node (ref "RV13") (pin "P$3") (pinfunction "A_P$3") (pintype "passive"))
      (node (ref "RV14") (pin "P$3") (pinfunction "A_P$3") (pintype "passive"))
      (node (ref "RV2") (pin "P$3") (pinfunction "A_P$3") (pintype "passive"))
      (node (ref "RV3") (pin "P$3") (pinfunction "A_P$3") (pintype "passive"))
      (node (ref "RV4") (pin "P$3") (pinfunction "A_P$3") (pintype "passive"))
      (node (ref "RV5") (pin "P$3") (pinfunction "A_P$3") (pintype "passive"))
      (node (ref "RV6") (pin "P$3") (pinfunction "A_P$3") (pintype "passive"))
      (node (ref "RV7") (pin "P$3") (pinfunction "A_P$3") (pintype "passive"))
      (node (ref "RV8") (pin "P$3") (pinfunction "A_P$3") (pintype "passive"))
      (node (ref "RV9") (pin "P$3") (pinfunction "A_P$3") (pintype "passive"))
      (node (ref "SUB1") (pin "RAGND") (pinfunction "AGND_RAGND") (pintype "bidirectional"))
      (node (ref "U1") (pin "7") (pinfunction "AGND_7") (pintype "bidirectional"))
    )
    (net (code "4") (name "AREF") (class "Default")
      (node (ref "RV1") (pin "P$1") (pinfunction "E_P$1") (pintype "passive"))
      (node (ref "RV10") (pin "P$1") (pinfunction "E_P$1") (pintype "passive"))
      (node (ref "RV11") (pin "P$1") (pinfunction "E_P$1") (pintype "passive"))
      (node (ref "RV12") (pin "P$1") (pinfunction "E_P$1") (pintype "passive"))
      (node (ref "RV13") (pin "P$1") (pinfunction "E_P$1") (pintype "passive"))
      (node (ref "RV14") (pin "P$1") (pinfunction "E_P$1") (pintype "passive"))
      (node (ref "RV2") (pin "P$1") (pinfunction "E_P$1") (pintype "passive"))
      (node (ref "RV3") (pin "P$1") (pinfunction "E_P$1") (pintype "passive"))
      (node (ref "RV4") (pin "P$1") (pinfunction "E_P$1") (pintype "passive"))
      (node (ref "RV5") (pin "P$1") (pinfunction "E_P$1") (pintype "passive"))
      (node (ref "RV6") (pin "P$1") (pinfunction "E_P$1") (pintype "passive"))
      (node (ref "RV7") (pin "P$1") (pinfunction "E_P$1") (pintype "passive"))
      (node (ref "RV8") (pin "P$1") (pinfunction "E_P$1") (pintype "passive"))
      (node (ref "RV9") (pin "P$1") (pinfunction "E_P$1") (pintype "passive"))
      (node (ref "SUB1") (pin "BAREF") (pinfunction "AREF_BAREF") (pintype "bidirectional"))
    )
    (net (code "5") (name "BCLK") (class "Default")
      (node (ref "SUB1") (pin "L9") (pinfunction "9_L9") (pintype "bidirectional"))
      (node (ref "U1") (pin "24") (pinfunction "BCLK_24") (pintype "bidirectional"))
    )
    (net (code "6") (name "CYM-DECAY") (class "Default")
      (node (ref "RV11") (pin "P$2") (pinfunction "S_P$2") (pintype "passive"))
      (node (ref "SUB1") (pin "B27") (pinfunction "27/A16_B27") (pintype "bidirectional"))
    )
    (net (code "7") (name "CYM-MIX") (class "Default")
      (node (ref "RV10") (pin "P$2") (pinfunction "S_P$2") (pintype "passive"))
      (node (ref "SUB1") (pin "EA14") (pinfunction "A14_EA14") (pintype "bidirectional"))
    )
    (net (code "8") (name "GND") (class "Default")
      (node (ref "C1") (pin "2") (pinfunction "2_2") (pintype "passive"))
      (node (ref "C11") (pin "2") (pinfunction "2_2") (pintype "passive"))
      (node (ref "C12") (pin "2") (pinfunction "2_2") (pintype "passive"))
      (node (ref "C13") (pin "2") (pinfunction "2_2") (pintype "passive"))
      (node (ref "C14") (pin "2") (pinfunction "2_2") (pintype "passive"))
      (node (ref "C2") (pin "2") (pinfunction "2_2") (pintype "passive"))
      (node (ref "C3") (pin "2") (pinfunction "2_2") (pintype "passive"))
      (node (ref "J5") (pin "2") (pinfunction "2_2") (pintype "bidirectional"))
      (node (ref "R1") (pin "1") (pinfunction "1_1") (pintype "passive"))
      (node (ref "R10") (pin "1") (pinfunction "1_1") (pintype "passive"))
      (node (ref "R11") (pin "1") (pinfunction "1_1") (pintype "passive"))
      (node (ref "R12") (pin "1") (pinfunction "1_1") (pintype "passive"))
      (node (ref "R13") (pin "1") (pinfunction "1_1") (pintype "passive"))
      (node (ref "R14") (pin "1") (pinfunction "1_1") (pintype "passive"))
      (node (ref "R15") (pin "1") (pinfunction "1_1") (pintype "passive"))
      (node (ref "R16") (pin "1") (pinfunction "1_1") (pintype "passive"))
      (node (ref "R17") (pin "1") (pinfunction "1_1") (pintype "passive"))
      (node (ref "R18") (pin "1") (pinfunction "1_1") (pintype "passive"))
      (node (ref "R19") (pin "1") (pinfunction "1_1") (pintype "passive"))
      (node (ref "R2") (pin "1") (pinfunction "1_1") (pintype "passive"))
      (node (ref "R20") (pin "1") (pinfunction "1_1") (pintype "passive"))
      (node (ref "R21") (pin "1") (pinfunction "1_1") (pintype "passive"))
      (node (ref "R22") (pin "1") (pinfunction "1_1") (pintype "passive"))
      (node (ref "R23") (pin "1") (pinfunction "1_1") (pintype "passive"))
      (node (ref "R24") (pin "1") (pinfunction "1_1") (pintype "passive"))
      (node (ref "R3") (pin "1") (pinfunction "1_1") (pintype "passive"))
      (node (ref "R4") (pin "1") (pinfunction "1_1") (pintype "passive"))
      (node (ref "R5") (pin "1") (pinfunction "1_1") (pintype "passive"))
      (node (ref "R6") (pin "1") (pinfunction "1_1") (pintype "passive"))
      (node (ref "R7") (pin "1") (pinfunction "1_1") (pintype "passive"))
      (node (ref "R8") (pin "1") (pinfunction "1_1") (pintype "passive"))
      (node (ref "R9") (pin "1") (pinfunction "1_1") (pintype "passive"))
      (node (ref "S1") (pin "3") (pinfunction "2_3") (pintype "passive"))
      (node (ref "S10") (pin "3") (pinfunction "2_3") (pintype "passive"))
      (node (ref "S11") (pin "3") (pinfunction "2_3") (pintype "passive"))
      (node (ref "S12") (pin "3") (pinfunction "2_3") (pintype "passive"))
      (node (ref "S13") (pin "3") (pinfunction "2_3") (pintype "passive"))
      (node (ref "S14") (pin "3") (pinfunction "2_3") (pintype "passive"))
      (node (ref "S15") (pin "3") (pinfunction "2_3") (pintype "passive"))
      (node (ref "S16") (pin "3") (pinfunction "2_3") (pintype "passive"))
      (node (ref "S17") (pin "3") (pinfunction "2_3") (pintype "passive"))
      (node (ref "S18") (pin "3") (pinfunction "2_3") (pintype "passive"))
      (node (ref "S19") (pin "3") (pinfunction "2_3") (pintype "passive"))
      (node (ref "S2") (pin "3") (pinfunction "2_3") (pintype "passive"))
      (node (ref "S20") (pin "3") (pinfunction "2_3") (pintype "passive"))
      (node (ref "S21") (pin "3") (pinfunction "2_3") (pintype "passive"))
      (node (ref "S22") (pin "3") (pinfunction "2_3") (pintype "passive"))
      (node (ref "S23") (pin "3") (pinfunction "2_3") (pintype "passive"))
      (node (ref "S24") (pin "3") (pinfunction "2_3") (pintype "passive"))
      (node (ref "S3") (pin "3") (pinfunction "2_3") (pintype "passive"))
      (node (ref "S4") (pin "3") (pinfunction "2_3") (pintype "passive"))
      (node (ref "S5") (pin "3") (pinfunction "2_3") (pintype "passive"))
      (node (ref "S6") (pin "3") (pinfunction "2_3") (pintype "passive"))
      (node (ref "S7") (pin "3") (pinfunction "2_3") (pintype "passive"))
      (node (ref "S8") (pin "3") (pinfunction "2_3") (pintype "passive"))
      (node (ref "S9") (pin "3") (pinfunction "2_3") (pintype "passive"))
      (node (ref "SUB1") (pin "BGND") (pinfunction "GND_BGND") (pintype "bidirectional"))
      (node (ref "SUB1") (pin "EGND") (pinfunction "GND_EGND") (pintype "bidirectional"))
      (node (ref "SUB1") (pin "LGND") (pinfunction "GND_LGND") (pintype "bidirectional"))
      (node (ref "U1") (pin "1") (pinfunction "GND_1") (pintype "bidirectional"))
      (node (ref "U1") (pin "3") (pinfunction "GND_3") (pintype "bidirectional"))
      (node (ref "U1") (pin "31") (pinfunction "ADDR_31") (pintype "bidirectional"))
      (node (ref "U1") (pin "32") (pinfunction "MODE_32") (pintype "bidirectional"))
      (node (ref "U1") (pin "EP") (pinfunction "GND_EP") (pintype "bidirectional"))
      (node (ref "U2") (pin "8") (pinfunction "GND_8") (pintype "bidirectional"))
      (node (ref "U3") (pin "8") (pinfunction "GND_8") (pintype "bidirectional"))
      (node (ref "U4") (pin "8") (pinfunction "GND_8") (pintype "bidirectional"))
      (node (ref "U5") (pin "8") (pinfunction "GND_8") (pintype "bidirectional"))
      (node (ref "U6") (pin "8") (pinfunction "GND_8") (pintype "bidirectional"))
      (node (ref "U7") (pin "8") (pinfunction "GND_8") (pintype "bidirectional"))
      (node (ref "U8") (pin "5") (pinfunction "GND_5") (pintype "bidirectional"))
      (node (ref "U9") (pin "1") (pinfunction "/OE_1") (pintype "bidirectional"))
      (node (ref "U9") (pin "3") (pinfunction "GND_3") (pintype "bidirectional"))
    )
    (net (code "9") (name "HAT-DECAY") (class "Default")
      (node (ref "RV12") (pin "P$2") (pinfunction "S_P$2") (pintype "passive"))
      (node (ref "SUB1") (pin "B28") (pinfunction "28/A17_B28") (pintype "bidirectional"))
    )
    (net (code "10") (name "I2CRX") (class "Default")
      (node (ref "SUB1") (pin "R13") (pinfunction "13_R13") (pintype "bidirectional"))
      (node (ref "U1") (pin "25") (pinfunction "RX_25") (pintype "bidirectional"))
    )
    (net (code "11") (name "I2CTX") (class "Default")
      (node (ref "SUB1") (pin "R22") (pinfunction "22/A8_R22") (pintype "bidirectional"))
      (node (ref "U1") (pin "26") (pinfunction "TX_26") (pintype "bidirectional"))
    )
    (net (code "12") (name "KIK-DECAY") (class "Default")
      (node (ref "RV3") (pin "P$2") (pinfunction "S_P$2") (pintype "passive"))
      (node (ref "SUB1") (pin "R17") (pinfunction "17/A3_R17") (pintype "bidirectional"))
    )
    (net (code "13") (name "KIK-MOD") (class "Default")
      (node (ref "RV2") (pin "P$2") (pinfunction "S_P$2") (pintype "passive"))
      (node (ref "SUB1") (pin "R16") (pinfunction "16/A2_R16") (pintype "bidirectional"))
    )
    (net (code "14") (name "KIK-PITCH") (class "Default")
      (node (ref "RV1") (pin "P$2") (pinfunction "S_P$2") (pintype "passive"))
      (node (ref "SUB1") (pin "R15") (pinfunction "15/A1_R15") (pintype "bidirectional"))
    )
    (net (code "15") (name "LRCLK") (class "Default")
      (node (ref "SUB1") (pin "R23") (pinfunction "23/A9_R23") (pintype "bidirectional"))
      (node (ref "U1") (pin "23") (pinfunction "LRCLK_23") (pintype "bidirectional"))
    )
    (net (code "16") (name "MCLK") (class "Default")
      (node (ref "SUB1") (pin "L11") (pinfunction "11_L11") (pintype "bidirectional"))
      (node (ref "U1") (pin "21") (pinfunction "MCLK_21") (pintype "bidirectional"))
    )
    (net (code "17") (name "Net-(C7-Pad2)") (class "Default")
      (node (ref "C7") (pin "2") (pinfunction "2_2") (pintype "passive"))
      (node (ref "J1") (pin "TIP") (pinfunction "TIP_TIP") (pintype "bidirectional"))
    )
    (net (code "18") (name "Net-(C8-Pad1)") (class "Default")
      (node (ref "C8") (pin "1") (pinfunction "1_1") (pintype "passive"))
      (node (ref "J2") (pin "TIP") (pinfunction "TIP_TIP") (pintype "bidirectional"))
    )
    (net (code "19") (name "Net-(C9-Pad1)") (class "Default")
      (node (ref "C9") (pin "1") (pinfunction "1_1") (pintype "passive"))
      (node (ref "J6") (pin "2") (pinfunction "2_2") (pintype "passive"))
    )
    (net (code "20") (name "Net-(C10-Pad1)") (class "Default")
      (node (ref "C10") (pin "1") (pinfunction "1_1") (pintype "passive"))
      (node (ref "J6") (pin "3") (pinfunction "3_3") (pintype "passive"))
    )
    (net (code "21") (name "Net-(D1-C)") (class "Default")
      (node (ref "D1") (pin "K") (pinfunction "C_K") (pintype "passive"))
      (node (ref "R1") (pin "2") (pinfunction "2_2") (pintype "passive"))
    )
    (net (code "22") (name "Net-(D2-C)") (class "Default")
      (node (ref "D2") (pin "K") (pinfunction "C_K") (pintype "passive"))
      (node (ref "R2") (pin "2") (pinfunction "2_2") (pintype "passive"))
    )
    (net (code "23") (name "Net-(D3-C)") (class "Default")
      (node (ref "D3") (pin "K") (pinfunction "C_K") (pintype "passive"))
      (node (ref "R3") (pin "2") (pinfunction "2_2") (pintype "passive"))
    )
    (net (code "24") (name "Net-(D4-C)") (class "Default")
      (node (ref "D4") (pin "K") (pinfunction "C_K") (pintype "passive"))
      (node (ref "R4") (pin "2") (pinfunction "2_2") (pintype "passive"))
    )
    (net (code "25") (name "Net-(D5-C)") (class "Default")
      (node (ref "D5") (pin "K") (pinfunction "C_K") (pintype "passive"))
      (node (ref "R5") (pin "2") (pinfunction "2_2") (pintype "passive"))
    )
    (net (code "26") (name "Net-(D6-C)") (class "Default")
      (node (ref "D6") (pin "K") (pinfunction "C_K") (pintype "passive"))
      (node (ref "R6") (pin "2") (pinfunction "2_2") (pintype "passive"))
    )
    (net (code "27") (name "Net-(D7-C)") (class "Default")
      (node (ref "D7") (pin "K") (pinfunction "C_K") (pintype "passive"))
      (node (ref "R7") (pin "2") (pinfunction "2_2") (pintype "passive"))
    )
    (net (code "28") (name "Net-(D8-C)") (class "Default")
      (node (ref "D8") (pin "K") (pinfunction "C_K") (pintype "passive"))
      (node (ref "R8") (pin "2") (pinfunction "2_2") (pintype "passive"))
    )
    (net (code "29") (name "Net-(D9-C)") (class "Default")
      (node (ref "D9") (pin "K") (pinfunction "C_K") (pintype "passive"))
      (node (ref "R17") (pin "2") (pinfunction "2_2") (pintype "passive"))
    )
    (net (code "30") (name "Net-(D10-C)") (class "Default")
      (node (ref "D10") (pin "K") (pinfunction "C_K") (pintype "passive"))
      (node (ref "R18") (pin "2") (pinfunction "2_2") (pintype "passive"))
    )
    (net (code "31") (name "Net-(D11-C)") (class "Default")
      (node (ref "D11") (pin "K") (pinfunction "C_K") (pintype "passive"))
      (node (ref "R19") (pin "2") (pinfunction "2_2") (pintype "passive"))
    )
    (net (code "32") (name "Net-(D12-C)") (class "Default")
      (node (ref "D12") (pin "K") (pinfunction "C_K") (pintype "passive"))
      (node (ref "R20") (pin "2") (pinfunction "2_2") (pintype "passive"))
    )
    (net (code "33") (name "Net-(D13-C)") (class "Default")
      (node (ref "D13") (pin "K") (pinfunction "C_K") (pintype "passive"))
      (node (ref "R21") (pin "2") (pinfunction "2_2") (pintype "passive"))
    )
    (net (code "34") (name "Net-(D14-C)") (class "Default")
      (node (ref "D14") (pin "K") (pinfunction "C_K") (pintype "passive"))
      (node (ref "R22") (pin "2") (pinfunction "2_2") (pintype "passive"))
    )
    (net (code "35") (name "Net-(D15-C)") (class "Default")
      (node (ref "D15") (pin "K") (pinfunction "C_K") (pintype "passive"))
      (node (ref "R23") (pin "2") (pinfunction "2_2") (pintype "passive"))
    )
    (net (code "36") (name "Net-(D16-C)") (class "Default")
      (node (ref "D16") (pin "K") (pinfunction "C_K") (pintype "passive"))
      (node (ref "R24") (pin "2") (pinfunction "2_2") (pintype "passive"))
    )
    (net (code "37") (name "Net-(D17-C)") (class "Default")
      (node (ref "D17") (pin "K") (pinfunction "C_K") (pintype "passive"))
      (node (ref "R9") (pin "2") (pinfunction "2_2") (pintype "passive"))
    )
    (net (code "38") (name "Net-(D18-C)") (class "Default")
      (node (ref "D18") (pin "K") (pinfunction "C_K") (pintype "passive"))
      (node (ref "R10") (pin "2") (pinfunction "2_2") (pintype "passive"))
    )
    (net (code "39") (name "Net-(D19-C)") (class "Default")
      (node (ref "D19") (pin "K") (pinfunction "C_K") (pintype "passive"))
      (node (ref "R11") (pin "2") (pinfunction "2_2") (pintype "passive"))
    )
    (net (code "40") (name "Net-(D20-C)") (class "Default")
      (node (ref "D20") (pin "K") (pinfunction "C_K") (pintype "passive"))
      (node (ref "R12") (pin "2") (pinfunction "2_2") (pintype "passive"))
    )
    (net (code "41") (name "Net-(D21-C)") (class "Default")
      (node (ref "D21") (pin "K") (pinfunction "C_K") (pintype "passive"))
      (node (ref "R13") (pin "2") (pinfunction "2_2") (pintype "passive"))
    )
    (net (code "42") (name "Net-(D22-C)") (class "Default")
      (node (ref "D22") (pin "K") (pinfunction "C_K") (pintype "passive"))
      (node (ref "R14") (pin "2") (pinfunction "2_2") (pintype "passive"))
    )
    (net (code "43") (name "Net-(D23-C)") (class "Default")
      (node (ref "D23") (pin "K") (pinfunction "C_K") (pintype "passive"))
      (node (ref "R15") (pin "2") (pinfunction "2_2") (pintype "passive"))
    )
    (net (code "44") (name "Net-(D24-C)") (class "Default")
      (node (ref "D24") (pin "K") (pinfunction "C_K") (pintype "passive"))
      (node (ref "R16") (pin "2") (pinfunction "2_2") (pintype "passive"))
    )
    (net (code "45") (name "Net-(J3-EARTH)") (class "Default")
      (node (ref "J3") (pin "SLEEVE") (pinfunction "EARTH_SLEEVE") (pintype "bidirectional"))
      (node (ref "U1") (pin "4") (pinfunction "HPGND_4") (pintype "bidirectional"))
    )
    (net (code "46") (name "Net-(J4-Pad4)") (class "Default")
      (node (ref "J4") (pin "4") (pinfunction "4_4") (pintype "bidirectional"))
      (node (ref "R25") (pin "1") (pinfunction "1_1") (pintype "passive"))
    )
    (net (code "47") (name "Net-(J5-Pad4)") (class "Default")
      (node (ref "J5") (pin "4") (pinfunction "4_4") (pintype "bidirectional"))
      (node (ref "R28") (pin "1") (pinfunction "1_1") (pintype "passive"))
    )
    (net (code "48") (name "Net-(J5-Pad5)") (class "Default")
      (node (ref "J5") (pin "5") (pinfunction "5_5") (pintype "bidirectional"))
      (node (ref "R27") (pin "2") (pinfunction "2_2") (pintype "passive"))
    )
    (net (code "49") (name "Net-(U1-HPL)") (class "Default")
      (node (ref "J3") (pin "TIP") (pinfunction "TIP_TIP") (pintype "bidirectional"))
      (node (ref "U1") (pin "6") (pinfunction "HPL_6") (pintype "bidirectional"))
    )
    (net (code "50") (name "Net-(U1-HPR)") (class "Default")
      (node (ref "J3") (pin "RING") (pinfunction "RING_RING") (pintype "bidirectional"))
      (node (ref "U1") (pin "2") (pinfunction "HPR_2") (pintype "bidirectional"))
    )
    (net (code "51") (name "Net-(U1-LINEINL)") (class "Default")
      (node (ref "C9") (pin "2") (pinfunction "2_2") (pintype "passive"))
      (node (ref "U1") (pin "14") (pinfunction "LINEINL_14") (pintype "bidirectional"))
    )
    (net (code "52") (name "Net-(U1-LINEINR)") (class "Default")
      (node (ref "C10") (pin "2") (pinfunction "2_2") (pintype "passive"))
      (node (ref "U1") (pin "13") (pinfunction "LINEINR_13") (pintype "bidirectional"))
    )
    (net (code "53") (name "Net-(U1-LINEOUTL)") (class "Default")
      (node (ref "C7") (pin "1") (pinfunction "1_1") (pintype "passive"))
      (node (ref "U1") (pin "12") (pinfunction "LINEOUTL_12") (pintype "bidirectional"))
    )
    (net (code "54") (name "Net-(U1-LINEOUTR)") (class "Default")
      (node (ref "C8") (pin "2") (pinfunction "2_2") (pintype "passive"))
      (node (ref "U1") (pin "11") (pinfunction "LINEOUTR_11") (pintype "bidirectional"))
    )
    (net (code "55") (name "Net-(U1-VAG)") (class "Default")
      (node (ref "C11") (pin "1") (pinfunction "1_1") (pintype "passive"))
      (node (ref "U1") (pin "10") (pinfunction "VAG_10") (pintype "bidirectional"))
    )
    (net (code "56") (name "Net-(U2-AIN)") (class "Default")
      (node (ref "R29") (pin "1") (pinfunction "1_1") (pintype "passive"))
      (node (ref "S1") (pin "1") (pinfunction "1_1") (pintype "passive"))
      (node (ref "U2") (pin "11") (pinfunction "AIN_11") (pintype "bidirectional"))
    )
    (net (code "57") (name "Net-(U2-BIN)") (class "Default")
      (node (ref "R30") (pin "1") (pinfunction "1_1") (pintype "passive"))
      (node (ref "S2") (pin "1") (pinfunction "1_1") (pintype "passive"))
      (node (ref "U2") (pin "12") (pinfunction "BIN_12") (pintype "bidirectional"))
    )
    (net (code "58") (name "Net-(U2-CIN)") (class "Default")
      (node (ref "R31") (pin "1") (pinfunction "1_1") (pintype "passive"))
      (node (ref "S3") (pin "1") (pinfunction "1_1") (pintype "passive"))
      (node (ref "U2") (pin "13") (pinfunction "CIN_13") (pintype "bidirectional"))
    )
    (net (code "59") (name "Net-(U2-DIN)") (class "Default")
      (node (ref "R32") (pin "1") (pinfunction "1_1") (pintype "passive"))
      (node (ref "S4") (pin "1") (pinfunction "1_1") (pintype "passive"))
      (node (ref "U2") (pin "14") (pinfunction "DIN_14") (pintype "bidirectional"))
    )
    (net (code "60") (name "Net-(U2-EIN)") (class "Default")
      (node (ref "R33") (pin "1") (pinfunction "1_1") (pintype "passive"))
      (node (ref "S5") (pin "1") (pinfunction "1_1") (pintype "passive"))
      (node (ref "U2") (pin "3") (pinfunction "EIN_3") (pintype "bidirectional"))
    )
    (net (code "61") (name "Net-(U2-FIN)") (class "Default")
      (node (ref "R34") (pin "1") (pinfunction "1_1") (pintype "passive"))
      (node (ref "S6") (pin "1") (pinfunction "1_1") (pintype "passive"))
      (node (ref "U2") (pin "4") (pinfunction "FIN_4") (pintype "bidirectional"))
    )
    (net (code "62") (name "Net-(U2-GIN)") (class "Default")
      (node (ref "R35") (pin "1") (pinfunction "1_1") (pintype "passive"))
      (node (ref "S7") (pin "1") (pinfunction "1_1") (pintype "passive"))
      (node (ref "U2") (pin "5") (pinfunction "GIN_5") (pintype "bidirectional"))
    )
    (net (code "63") (name "Net-(U2-HIN)") (class "Default")
      (node (ref "R36") (pin "1") (pinfunction "1_1") (pintype "passive"))
      (node (ref "S8") (pin "1") (pinfunction "1_1") (pintype "passive"))
      (node (ref "U2") (pin "6") (pinfunction "HIN_6") (pintype "bidirectional"))
    )
    (net (code "64") (name "Net-(U3-AIN)") (class "Default")
      (node (ref "R37") (pin "1") (pinfunction "1_1") (pintype "passive"))
      (node (ref "S9") (pin "1") (pinfunction "1_1") (pintype "passive"))
      (node (ref "U3") (pin "11") (pinfunction "AIN_11") (pintype "bidirectional"))
    )
    (net (code "65") (name "Net-(U3-BIN)") (class "Default")
      (node (ref "R38") (pin "1") (pinfunction "1_1") (pintype "passive"))
      (node (ref "S10") (pin "1") (pinfunction "1_1") (pintype "passive"))
      (node (ref "U3") (pin "12") (pinfunction "BIN_12") (pintype "bidirectional"))
    )
    (net (code "66") (name "Net-(U3-CIN)") (class "Default")
      (node (ref "R39") (pin "1") (pinfunction "1_1") (pintype "passive"))
      (node (ref "S11") (pin "1") (pinfunction "1_1") (pintype "passive"))
      (node (ref "U3") (pin "13") (pinfunction "CIN_13") (pintype "bidirectional"))
    )
    (net (code "67") (name "Net-(U3-DIN)") (class "Default")
      (node (ref "R40") (pin "1") (pinfunction "1_1") (pintype "passive"))
      (node (ref "S12") (pin "1") (pinfunction "1_1") (pintype "passive"))
      (node (ref "U3") (pin "14") (pinfunction "DIN_14") (pintype "bidirectional"))
    )
    (net (code "68") (name "Net-(U3-EIN)") (class "Default")
      (node (ref "R41") (pin "1") (pinfunction "1_1") (pintype "passive"))
      (node (ref "S13") (pin "1") (pinfunction "1_1") (pintype "passive"))
      (node (ref "U3") (pin "3") (pinfunction "EIN_3") (pintype "bidirectional"))
    )
    (net (code "69") (name "Net-(U3-FIN)") (class "Default")
      (node (ref "R42") (pin "1") (pinfunction "1_1") (pintype "passive"))
      (node (ref "S14") (pin "1") (pinfunction "1_1") (pintype "passive"))
      (node (ref "U3") (pin "4") (pinfunction "FIN_4") (pintype "bidirectional"))
    )
    (net (code "70") (name "Net-(U3-GIN)") (class "Default")
      (node (ref "R43") (pin "1") (pinfunction "1_1") (pintype "passive"))
      (node (ref "S15") (pin "1") (pinfunction "1_1") (pintype "passive"))
      (node (ref "U3") (pin "5") (pinfunction "GIN_5") (pintype "bidirectional"))
    )
    (net (code "71") (name "Net-(U3-HIN)") (class "Default")
      (node (ref "R44") (pin "1") (pinfunction "1_1") (pintype "passive"))
      (node (ref "S16") (pin "1") (pinfunction "1_1") (pintype "passive"))
      (node (ref "U3") (pin "6") (pinfunction "HIN_6") (pintype "bidirectional"))
    )
    (net (code "72") (name "Net-(U4-AIN)") (class "Default")
      (node (ref "R45") (pin "1") (pinfunction "1_1") (pintype "passive"))
      (node (ref "S17") (pin "1") (pinfunction "1_1") (pintype "passive"))
      (node (ref "U4") (pin "11") (pinfunction "AIN_11") (pintype "bidirectional"))
    )
    (net (code "73") (name "Net-(U4-BIN)") (class "Default")
      (node (ref "R46") (pin "1") (pinfunction "1_1") (pintype "passive"))
      (node (ref "S18") (pin "1") (pinfunction "1_1") (pintype "passive"))
      (node (ref "U4") (pin "12") (pinfunction "BIN_12") (pintype "bidirectional"))
    )
    (net (code "74") (name "Net-(U4-CIN)") (class "Default")
      (node (ref "R47") (pin "1") (pinfunction "1_1") (pintype "passive"))
      (node (ref "S19") (pin "1") (pinfunction "1_1") (pintype "passive"))
      (node (ref "U4") (pin "13") (pinfunction "CIN_13") (pintype "bidirectional"))
    )
    (net (code "75") (name "Net-(U4-DIN)") (class "Default")
      (node (ref "R48") (pin "1") (pinfunction "1_1") (pintype "passive"))
      (node (ref "S20") (pin "1") (pinfunction "1_1") (pintype "passive"))
      (node (ref "U4") (pin "14") (pinfunction "DIN_14") (pintype "bidirectional"))
    )
    (net (code "76") (name "Net-(U4-EIN)") (class "Default")
      (node (ref "R49") (pin "1") (pinfunction "1_1") (pintype "passive"))
      (node (ref "S21") (pin "1") (pinfunction "1_1") (pintype "passive"))
      (node (ref "U4") (pin "3") (pinfunction "EIN_3") (pintype "bidirectional"))
    )
    (net (code "77") (name "Net-(U4-FIN)") (class "Default")
      (node (ref "R50") (pin "1") (pinfunction "1_1") (pintype "passive"))
      (node (ref "S22") (pin "1") (pinfunction "1_1") (pintype "passive"))
      (node (ref "U4") (pin "4") (pinfunction "FIN_4") (pintype "bidirectional"))
    )
    (net (code "78") (name "Net-(U4-GIN)") (class "Default")
      (node (ref "R51") (pin "1") (pinfunction "1_1") (pintype "passive"))
      (node (ref "S23") (pin "1") (pinfunction "1_1") (pintype "passive"))
      (node (ref "U4") (pin "5") (pinfunction "GIN_5") (pintype "bidirectional"))
    )
    (net (code "79") (name "Net-(U4-HIN)") (class "Default")
      (node (ref "R52") (pin "1") (pinfunction "1_1") (pintype "passive"))
      (node (ref "S24") (pin "1") (pinfunction "1_1") (pintype "passive"))
      (node (ref "U4") (pin "6") (pinfunction "HIN_6") (pintype "bidirectional"))
    )
    (net (code "80") (name "Net-(U5-AOUT)") (class "Default")
      (node (ref "D8") (pin "A") (pinfunction "A_A") (pintype "passive"))
      (node (ref "U5") (pin "15") (pinfunction "AOUT_15") (pintype "bidirectional"))
    )
    (net (code "81") (name "Net-(U5-BOUT)") (class "Default")
      (node (ref "D7") (pin "A") (pinfunction "A_A") (pintype "passive"))
      (node (ref "U5") (pin "1") (pinfunction "BOUT_1") (pintype "bidirectional"))
    )
    (net (code "82") (name "Net-(U5-COUT)") (class "Default")
      (node (ref "D6") (pin "A") (pinfunction "A_A") (pintype "passive"))
      (node (ref "U5") (pin "2") (pinfunction "COUT_2") (pintype "bidirectional"))
    )
    (net (code "83") (name "Net-(U5-DOUT)") (class "Default")
      (node (ref "D5") (pin "A") (pinfunction "A_A") (pintype "passive"))
      (node (ref "U5") (pin "3") (pinfunction "DOUT_3") (pintype "bidirectional"))
    )
    (net (code "84") (name "Net-(U5-EOUT)") (class "Default")
      (node (ref "D4") (pin "A") (pinfunction "A_A") (pintype "passive"))
      (node (ref "U5") (pin "4") (pinfunction "EOUT_4") (pintype "bidirectional"))
    )
    (net (code "85") (name "Net-(U5-FOUT)") (class "Default")
      (node (ref "D3") (pin "A") (pinfunction "A_A") (pintype "passive"))
      (node (ref "U5") (pin "5") (pinfunction "FOUT_5") (pintype "bidirectional"))
    )
    (net (code "86") (name "Net-(U5-GOUT)") (class "Default")
      (node (ref "D2") (pin "A") (pinfunction "A_A") (pintype "passive"))
      (node (ref "U5") (pin "6") (pinfunction "GOUT_6") (pintype "bidirectional"))
    )
    (net (code "87") (name "Net-(U5-HOUT)") (class "Default")
      (node (ref "D1") (pin "A") (pinfunction "A_A") (pintype "passive"))
      (node (ref "U5") (pin "7") (pinfunction "HOUT_7") (pintype "bidirectional"))
    )
    (net (code "88") (name "Net-(U6-AOUT)") (class "Default")
      (node (ref "D16") (pin "A") (pinfunction "A_A") (pintype "passive"))
      (node (ref "U6") (pin "15") (pinfunction "AOUT_15") (pintype "bidirectional"))
    )
    (net (code "89") (name "Net-(U6-BOUT)") (class "Default")
      (node (ref "D15") (pin "A") (pinfunction "A_A") (pintype "passive"))
      (node (ref "U6") (pin "1") (pinfunction "BOUT_1") (pintype "bidirectional"))
    )
    (net (code "90") (name "Net-(U6-COUT)") (class "Default")
      (node (ref "D14") (pin "A") (pinfunction "A_A") (pintype "passive"))
      (node (ref "U6") (pin "2") (pinfunction "COUT_2") (pintype "bidirectional"))
    )
    (net (code "91") (name "Net-(U6-DOUT)") (class "Default")
      (node (ref "D13") (pin "A") (pinfunction "A_A") (pintype "passive"))
      (node (ref "U6") (pin "3") (pinfunction "DOUT_3") (pintype "bidirectional"))
    )
    (net (code "92") (name "Net-(U6-EOUT)") (class "Default")
      (node (ref "D12") (pin "A") (pinfunction "A_A") (pintype "passive"))
      (node (ref "U6") (pin "4") (pinfunction "EOUT_4") (pintype "bidirectional"))
    )
    (net (code "93") (name "Net-(U6-FOUT)") (class "Default")
      (node (ref "D11") (pin "A") (pinfunction "A_A") (pintype "passive"))
      (node (ref "U6") (pin "5") (pinfunction "FOUT_5") (pintype "bidirectional"))
    )
    (net (code "94") (name "Net-(U6-GOUT)") (class "Default")
      (node (ref "D10") (pin "A") (pinfunction "A_A") (pintype "passive"))
      (node (ref "U6") (pin "6") (pinfunction "GOUT_6") (pintype "bidirectional"))
    )
    (net (code "95") (name "Net-(U6-HOUT)") (class "Default")
      (node (ref "D9") (pin "A") (pinfunction "A_A") (pintype "passive"))
      (node (ref "U6") (pin "7") (pinfunction "HOUT_7") (pintype "bidirectional"))
    )
    (net (code "96") (name "Net-(U7-AOUT)") (class "Default")
      (node (ref "D24") (pin "A") (pinfunction "A_A") (pintype "passive"))
      (node (ref "U7") (pin "15") (pinfunction "AOUT_15") (pintype "bidirectional"))
    )
    (net (code "97") (name "Net-(U7-BOUT)") (class "Default")
      (node (ref "D23") (pin "A") (pinfunction "A_A") (pintype "passive"))
      (node (ref "U7") (pin "1") (pinfunction "BOUT_1") (pintype "bidirectional"))
    )
    (net (code "98") (name "Net-(U7-COUT)") (class "Default")
      (node (ref "D22") (pin "A") (pinfunction "A_A") (pintype "passive"))
      (node (ref "U7") (pin "2") (pinfunction "COUT_2") (pintype "bidirectional"))
    )
    (net (code "99") (name "Net-(U7-DOUT)") (class "Default")
      (node (ref "D21") (pin "A") (pinfunction "A_A") (pintype "passive"))
      (node (ref "U7") (pin "3") (pinfunction "DOUT_3") (pintype "bidirectional"))
    )
    (net (code "100") (name "Net-(U7-EOUT)") (class "Default")
      (node (ref "D20") (pin "A") (pinfunction "A_A") (pintype "passive"))
      (node (ref "U7") (pin "4") (pinfunction "EOUT_4") (pintype "bidirectional"))
    )
    (net (code "101") (name "Net-(U7-FOUT)") (class "Default")
      (node (ref "D19") (pin "A") (pinfunction "A_A") (pintype "passive"))
      (node (ref "U7") (pin "5") (pinfunction "FOUT_5") (pintype "bidirectional"))
    )
    (net (code "102") (name "Net-(U7-GOUT)") (class "Default")
      (node (ref "D18") (pin "A") (pinfunction "A_A") (pintype "passive"))
      (node (ref "U7") (pin "6") (pinfunction "GOUT_6") (pintype "bidirectional"))
    )
    (net (code "103") (name "Net-(U7-HOUT)") (class "Default")
      (node (ref "D17") (pin "A") (pinfunction "A_A") (pintype "passive"))
      (node (ref "U7") (pin "7") (pinfunction "HOUT_7") (pintype "bidirectional"))
    )
    (net (code "104") (name "Net-(U8-A)") (class "Default")
      (node (ref "D25") (pin "C") (pinfunction "C_C") (pintype "passive"))
      (node (ref "R25") (pin "2") (pinfunction "2_2") (pintype "passive"))
      (node (ref "U8") (pin "2") (pinfunction "A_2") (pintype "bidirectional"))
    )
    (net (code "105") (name "Net-(U8-C)") (class "Default")
      (node (ref "D25") (pin "A") (pinfunction "A_A") (pintype "passive"))
      (node (ref "J4") (pin "5") (pinfunction "5_5") (pintype "bidirectional"))
      (node (ref "U8") (pin "3") (pinfunction "C_3") (pintype "bidirectional"))
    )
    (net (code "106") (name "Net-(U8-VOUT)") (class "Default")
      (node (ref "R26") (pin "1") (pinfunction "1_1") (pintype "passive"))
      (node (ref "U8") (pin "6") (pinfunction "VOUT_6") (pintype "bidirectional"))
    )
    (net (code "107") (name "Net-(U9-Y)") (class "Default")
      (node (ref "R27") (pin "1") (pinfunction "1_1") (pintype "passive"))
      (node (ref "U9") (pin "4") (pinfunction "Y_4") (pintype "bidirectional"))
    )
    (net (code "108") (name "SCL") (class "Default")
      (node (ref "SUB1") (pin "R19") (pinfunction "19/A5_R19") (pintype "bidirectional"))
      (node (ref "U1") (pin "29") (pinfunction "SCL_29") (pintype "bidirectional"))
    )
    (net (code "109") (name "SDA") (class "Default")
      (node (ref "SUB1") (pin "R18") (pinfunction "18/A4_R18") (pintype "bidirectional"))
      (node (ref "U1") (pin "27") (pinfunction "SDA_27") (pintype "bidirectional"))
    )
    (net (code "110") (name "SNR-DECAY") (class "Default")
      (node (ref "RV6") (pin "P$2") (pinfunction "S_P$2") (pintype "passive"))
      (node (ref "SUB1") (pin "BA10") (pinfunction "A10_BA10") (pintype "bidirectional"))
    )
    (net (code "111") (name "SNR-MIX") (class "Default")
      (node (ref "RV5") (pin "P$2") (pinfunction "S_P$2") (pintype "passive"))
      (node (ref "SUB1") (pin "R21") (pinfunction "21/A7_R21") (pintype "bidirectional"))
    )
    (net (code "112") (name "SNR-PITCH") (class "Default")
      (node (ref "RV4") (pin "P$2") (pinfunction "S_P$2") (pintype "passive"))
      (node (ref "SUB1") (pin "R20") (pinfunction "20/A6_R20") (pintype "bidirectional"))
    )
    (net (code "113") (name "TEMPO") (class "Default")
      (node (ref "RV14") (pin "P$2") (pinfunction "S_P$2") (pintype "passive"))
      (node (ref "SUB1") (pin "B29") (pinfunction "29/A18_B29") (pintype "bidirectional"))
    )
    (net (code "114") (name "TOM-2ND") (class "Default")
      (node (ref "RV8") (pin "P$2") (pinfunction "S_P$2") (pintype "passive"))
      (node (ref "SUB1") (pin "BA12") (pinfunction "A12_BA12") (pintype "bidirectional"))
    )
    (net (code "115") (name "TOM-DECAY") (class "Default")
      (node (ref "RV9") (pin "P$2") (pinfunction "S_P$2") (pintype "passive"))
      (node (ref "SUB1") (pin "BA13") (pinfunction "A13_BA13") (pintype "bidirectional"))
    )
    (net (code "116") (name "TOM-PITCH") (class "Default")
      (node (ref "RV7") (pin "P$2") (pinfunction "S_P$2") (pintype "passive"))
      (node (ref "SUB1") (pin "BA11") (pinfunction "A11_BA11") (pintype "bidirectional"))
    )
    (net (code "117") (name "VOLUME") (class "Default")
      (node (ref "RV13") (pin "P$2") (pinfunction "S_P$2") (pintype "passive"))
      (node (ref "SUB1") (pin "B30") (pinfunction "30/A19_B30") (pintype "bidirectional"))
    )
    (net (code "118") (name "unconnected-(J1-EARTH-NORM-PadSLEEVE-NORM)") (class "Default")
      (node (ref "J1") (pin "SLEEVE-NORM") (pinfunction "EARTH-NORM_SLEEVE-NORM") (pintype "bidirectional"))
    )
    (net (code "119") (name "unconnected-(J1-PadRING)") (class "Default")
      (node (ref "J1") (pin "RING") (pinfunction "RING_RING") (pintype "bidirectional"))
    )
    (net (code "120") (name "unconnected-(J1-PadRING-NORM)") (class "Default")
      (node (ref "J1") (pin "RING-NORM") (pinfunction "RING-NORM_RING-NORM") (pintype "bidirectional"))
    )
    (net (code "121") (name "unconnected-(J1-PadTIP-NORM)") (class "Default")
      (node (ref "J1") (pin "TIP-NORM") (pinfunction "TIP-NORM_TIP-NORM") (pintype "bidirectional"))
    )
    (net (code "122") (name "unconnected-(J2-EARTH-NORM-PadSLEEVE-NORM)") (class "Default")
      (node (ref "J2") (pin "SLEEVE-NORM") (pinfunction "EARTH-NORM_SLEEVE-NORM") (pintype "bidirectional"))
    )
    (net (code "123") (name "unconnected-(J2-PadRING)") (class "Default")
      (node (ref "J2") (pin "RING") (pinfunction "RING_RING") (pintype "bidirectional"))
    )
    (net (code "124") (name "unconnected-(J2-PadRING-NORM)") (class "Default")
      (node (ref "J2") (pin "RING-NORM") (pinfunction "RING-NORM_RING-NORM") (pintype "bidirectional"))
    )
    (net (code "125") (name "unconnected-(J2-PadTIP-NORM)") (class "Default")
      (node (ref "J2") (pin "TIP-NORM") (pinfunction "TIP-NORM_TIP-NORM") (pintype "bidirectional"))
    )
    (net (code "126") (name "unconnected-(J3-EARTH-NORM-PadSLEEVE-NORM)") (class "Default")
      (node (ref "J3") (pin "SLEEVE-NORM") (pinfunction "EARTH-NORM_SLEEVE-NORM") (pintype "bidirectional"))
    )
    (net (code "127") (name "unconnected-(J3-PadRING-NORM)") (class "Default")
      (node (ref "J3") (pin "RING-NORM") (pinfunction "RING-NORM_RING-NORM") (pintype "bidirectional"))
    )
    (net (code "128") (name "unconnected-(J3-PadTIP-NORM)") (class "Default")
      (node (ref "J3") (pin "TIP-NORM") (pinfunction "TIP-NORM_TIP-NORM") (pintype "bidirectional"))
    )
    (net (code "129") (name "unconnected-(J4-Pad1)") (class "Default")
      (node (ref "J4") (pin "1") (pinfunction "1_1") (pintype "bidirectional"))
    )
    (net (code "130") (name "unconnected-(J4-Pad2)") (class "Default")
      (node (ref "J4") (pin "2") (pinfunction "2_2") (pintype "bidirectional"))
    )
    (net (code "131") (name "unconnected-(J4-Pad3)") (class "Default")
      (node (ref "J4") (pin "3") (pinfunction "3_3") (pintype "bidirectional"))
    )
    (net (code "132") (name "unconnected-(J5-Pad1)") (class "Default")
      (node (ref "J5") (pin "1") (pinfunction "1_1") (pintype "bidirectional"))
    )
    (net (code "133") (name "unconnected-(J5-Pad3)") (class "Default")
      (node (ref "J5") (pin "3") (pinfunction "3_3") (pintype "bidirectional"))
    )
    (net (code "134") (name "unconnected-(SUB1A-3.3V-PadB3.3)") (class "Default")
      (node (ref "SUB1") (pin "B3.3") (pinfunction "3.3V_B3.3") (pintype "bidirectional"))
    )
    (net (code "135") (name "unconnected-(SUB1A-24-PadB24)") (class "Default")
      (node (ref "SUB1") (pin "B24") (pinfunction "24_B24") (pintype "bidirectional"))
    )
    (net (code "136") (name "unconnected-(SUB1A-25-PadB25)") (class "Default")
      (node (ref "SUB1") (pin "B25") (pinfunction "25_B25") (pintype "bidirectional"))
    )
    (net (code "137") (name "unconnected-(SUB1A-26{slash}A15-PadB26)") (class "Default")
      (node (ref "SUB1") (pin "B26") (pinfunction "26/A15_B26") (pintype "bidirectional"))
    )
    (net (code "138") (name "unconnected-(SUB1A-31{slash}A20-PadB31)") (class "Default")
      (node (ref "SUB1") (pin "B31") (pinfunction "31/A20_B31") (pintype "bidirectional"))
    )
    (net (code "139") (name "unconnected-(SUB1A-32-PadB32)") (class "Default")
      (node (ref "SUB1") (pin "B32") (pinfunction "32_B32") (pintype "bidirectional"))
    )
    (net (code "140") (name "unconnected-(SUB1A-33-PadB33)") (class "Default")
      (node (ref "SUB1") (pin "B33") (pinfunction "33_B33") (pintype "bidirectional"))
    )
    (net (code "141") (name "unconnected-(SUB1A-VUSB-PadBVUSB)") (class "Default")
      (node (ref "SUB1") (pin "BVUSB") (pinfunction "VUSB_BVUSB") (pintype "bidirectional"))
    )
    (net (code "142") (name "unconnected-(SUB1B-0-PadL0)") (class "Default")
      (node (ref "SUB1") (pin "L0") (pinfunction "0_L0") (pintype "bidirectional"))
    )
    (net (code "143") (name "unconnected-(SUB1B-1-PadL1)") (class "Default")
      (node (ref "SUB1") (pin "L1") (pinfunction "1_L1") (pintype "bidirectional"))
    )
    (net (code "144") (name "unconnected-(SUB1B-2-PadL2)") (class "Default")
      (node (ref "SUB1") (pin "L2") (pinfunction "2_L2") (pintype "bidirectional"))
    )
    (net (code "145") (name "unconnected-(SUB1B-3-PadL3)") (class "Default")
      (node (ref "SUB1") (pin "L3") (pinfunction "3_L3") (pintype "bidirectional"))
    )
    (net (code "146") (name "unconnected-(SUB1B-3.3V-PadR3.3)") (class "Default")
      (node (ref "SUB1") (pin "R3.3") (pinfunction "3.3V_R3.3") (pintype "bidirectional"))
    )
    (net (code "147") (name "unconnected-(SUB1B-4-PadL4)") (class "Default")
      (node (ref "SUB1") (pin "L4") (pinfunction "4_L4") (pintype "bidirectional"))
    )
    (net (code "148") (name "unconnected-(SUB1B-5-PadL5)") (class "Default")
      (node (ref "SUB1") (pin "L5") (pinfunction "5_L5") (pintype "bidirectional"))
    )
    (net (code "149") (name "unconnected-(SUB1B-6-PadL6)") (class "Default")
      (node (ref "SUB1") (pin "L6") (pinfunction "6_L6") (pintype "bidirectional"))
    )
    (net (code "150") (name "unconnected-(SUB1B-7-PadL7)") (class "Default")
      (node (ref "SUB1") (pin "L7") (pinfunction "7_L7") (pintype "bidirectional"))
    )
    (net (code "151") (name "unconnected-(SUB1B-8-PadL8)") (class "Default")
      (node (ref "SUB1") (pin "L8") (pinfunction "8_L8") (pintype "bidirectional"))
    )
    (net (code "152") (name "unconnected-(SUB1B-10-PadL10)") (class "Default")
      (node (ref "SUB1") (pin "L10") (pinfunction "10_L10") (pintype "bidirectional"))
    )
    (net (code "153") (name "unconnected-(SUB1B-12-PadL12)") (class "Default")
      (node (ref "SUB1") (pin "L12") (pinfunction "12_L12") (pintype "bidirectional"))
    )
    (net (code "154") (name "unconnected-(SUB1B-14{slash}A0-PadR14)") (class "Default")
      (node (ref "SUB1") (pin "R14") (pinfunction "14/A0_R14") (pintype "bidirectional"))
    )
    (net (code "155") (name "unconnected-(SUB1B-VIN-PadRVIN)") (class "Default")
      (node (ref "SUB1") (pin "RVIN") (pinfunction "VIN_RVIN") (pintype "bidirectional"))
    )
    (net (code "156") (name "unconnected-(SUB1C-3.3V-PadE3.3)") (class "Default")
      (node (ref "SUB1") (pin "E3.3") (pinfunction "3.3V_E3.3") (pintype "bidirectional"))
    )
    (net (code "157") (name "unconnected-(SUB1C-PROG-PadEPROG)") (class "Default")
      (node (ref "SUB1") (pin "EPROG") (pinfunction "PROG_EPROG") (pintype "bidirectional"))
    )
    (net (code "158") (name "unconnected-(SUB1C-VBAT-PadEVBAT)") (class "Default")
      (node (ref "SUB1") (pin "EVBAT") (pinfunction "VBAT_EVBAT") (pintype "bidirectional"))
    )
    (net (code "159") (name "unconnected-(U1-CPFLT-Pad18)") (class "Default")
      (node (ref "U1") (pin "18") (pinfunction "CPFLT_18") (pintype "bidirectional"))
    )
    (net (code "160") (name "unconnected-(U1-MIC-Pad15)") (class "Default")
      (node (ref "U1") (pin "15") (pinfunction "MIC_15") (pintype "bidirectional"))
    )
    (net (code "161") (name "unconnected-(U1-MICBIAS-Pad16)") (class "Default")
      (node (ref "U1") (pin "16") (pinfunction "MICBIAS_16") (pintype "bidirectional"))
    )
    (net (code "162") (name "unconnected-(U1-VDDA-Pad5)") (class "Default")
      (node (ref "U1") (pin "5") (pinfunction "VDDA_5") (pintype "bidirectional"))
    )
    (net (code "163") (name "unconnected-(U1-VDDD-Pad30)") (class "Default")
      (node (ref "U1") (pin "30") (pinfunction "VDDD_30") (pintype "bidirectional"))
    )
    (net (code "164") (name "unconnected-(U1-VDDIO-Pad20)") (class "Default")
      (node (ref "U1") (pin "20") (pinfunction "VDDIO_20") (pintype "bidirectional"))
    )
    (net (code "165") (name "unconnected-(U2-CLK-Pad2)") (class "Default")
      (node (ref "U2") (pin "2") (pinfunction "CLK_2") (pintype "bidirectional"))
    )
    (net (code "166") (name "unconnected-(U2-CLK_INH-Pad15)") (class "Default")
      (node (ref "U2") (pin "15") (pinfunction "CLK_INH_15") (pintype "bidirectional"))
    )
    (net (code "167") (name "unconnected-(U2-Q-Pad9)") (class "Default")
      (node (ref "U2") (pin "9") (pinfunction "Q_9") (pintype "bidirectional"))
    )
    (net (code "168") (name "unconnected-(U2-SER_IN-Pad10)") (class "Default")
      (node (ref "U2") (pin "10") (pinfunction "SER_IN_10") (pintype "bidirectional"))
    )
    (net (code "169") (name "unconnected-(U2-SH{slash}~{LD}-Pad1)") (class "Default")
      (node (ref "U2") (pin "1") (pinfunction "SH/~{LD}_1") (pintype "bidirectional"))
    )
    (net (code "170") (name "unconnected-(U2-~{Q}-Pad7)") (class "Default")
      (node (ref "U2") (pin "7") (pinfunction "~{Q}_7") (pintype "bidirectional"))
    )
    (net (code "171") (name "unconnected-(U3-CLK-Pad2)") (class "Default")
      (node (ref "U3") (pin "2") (pinfunction "CLK_2") (pintype "bidirectional"))
    )
    (net (code "172") (name "unconnected-(U3-CLK_INH-Pad15)") (class "Default")
      (node (ref "U3") (pin "15") (pinfunction "CLK_INH_15") (pintype "bidirectional"))
    )
    (net (code "173") (name "unconnected-(U3-Q-Pad9)") (class "Default")
      (node (ref "U3") (pin "9") (pinfunction "Q_9") (pintype "bidirectional"))
    )
    (net (code "174") (name "unconnected-(U3-SER_IN-Pad10)") (class "Default")
      (node (ref "U3") (pin "10") (pinfunction "SER_IN_10") (pintype "bidirectional"))
    )
    (net (code "175") (name "unconnected-(U3-SH{slash}~{LD}-Pad1)") (class "Default")
      (node (ref "U3") (pin "1") (pinfunction "SH/~{LD}_1") (pintype "bidirectional"))
    )
    (net (code "176") (name "unconnected-(U3-~{Q}-Pad7)") (class "Default")
      (node (ref "U3") (pin "7") (pinfunction "~{Q}_7") (pintype "bidirectional"))
    )
    (net (code "177") (name "unconnected-(U4-CLK-Pad2)") (class "Default")
      (node (ref "U4") (pin "2") (pinfunction "CLK_2") (pintype "bidirectional"))
    )
    (net (code "178") (name "unconnected-(U4-CLK_INH-Pad15)") (class "Default")
      (node (ref "U4") (pin "15") (pinfunction "CLK_INH_15") (pintype "bidirectional"))
    )
    (net (code "179") (name "unconnected-(U4-Q-Pad9)") (class "Default")
      (node (ref "U4") (pin "9") (pinfunction "Q_9") (pintype "bidirectional"))
    )
    (net (code "180") (name "unconnected-(U4-SER_IN-Pad10)") (class "Default")
      (node (ref "U4") (pin "10") (pinfunction "SER_IN_10") (pintype "bidirectional"))
    )
    (net (code "181") (name "unconnected-(U4-SH{slash}~{LD}-Pad1)") (class "Default")
      (node (ref "U4") (pin "1") (pinfunction "SH/~{LD}_1") (pintype "bidirectional"))
    )
    (net (code "182") (name "unconnected-(U4-~{Q}-Pad7)") (class "Default")
      (node (ref "U4") (pin "7") (pinfunction "~{Q}_7") (pintype "bidirectional"))
    )
    (net (code "183") (name "unconnected-(U5-RCLK-Pad12)") (class "Default")
      (node (ref "U5") (pin "12") (pinfunction "RCLK_12") (pintype "bidirectional"))
    )
    (net (code "184") (name "unconnected-(U5-SER_IN-Pad14)") (class "Default")
      (node (ref "U5") (pin "14") (pinfunction "SER_IN_14") (pintype "bidirectional"))
    )
    (net (code "185") (name "unconnected-(U5-SRCLK-Pad11)") (class "Default")
      (node (ref "U5") (pin "11") (pinfunction "SRCLK_11") (pintype "bidirectional"))
    )
    (net (code "186") (name "unconnected-(U5-~{OE}-Pad13)") (class "Default")
      (node (ref "U5") (pin "13") (pinfunction "~{OE}_13") (pintype "bidirectional"))
    )
    (net (code "187") (name "unconnected-(U5-~{QH}-Pad9)") (class "Default")
      (node (ref "U5") (pin "9") (pinfunction "~{QH}_9") (pintype "bidirectional"))
    )
    (net (code "188") (name "unconnected-(U5-~{SPCLR}-Pad10)") (class "Default")
      (node (ref "U5") (pin "10") (pinfunction "~{SPCLR}_10") (pintype "bidirectional"))
    )
    (net (code "189") (name "unconnected-(U6-RCLK-Pad12)") (class "Default")
      (node (ref "U6") (pin "12") (pinfunction "RCLK_12") (pintype "bidirectional"))
    )
    (net (code "190") (name "unconnected-(U6-SER_IN-Pad14)") (class "Default")
      (node (ref "U6") (pin "14") (pinfunction "SER_IN_14") (pintype "bidirectional"))
    )
    (net (code "191") (name "unconnected-(U6-SRCLK-Pad11)") (class "Default")
      (node (ref "U6") (pin "11") (pinfunction "SRCLK_11") (pintype "bidirectional"))
    )
    (net (code "192") (name "unconnected-(U6-~{OE}-Pad13)") (class "Default")
      (node (ref "U6") (pin "13") (pinfunction "~{OE}_13") (pintype "bidirectional"))
    )
    (net (code "193") (name "unconnected-(U6-~{QH}-Pad9)") (class "Default")
      (node (ref "U6") (pin "9") (pinfunction "~{QH}_9") (pintype "bidirectional"))
    )
    (net (code "194") (name "unconnected-(U6-~{SPCLR}-Pad10)") (class "Default")
      (node (ref "U6") (pin "10") (pinfunction "~{SPCLR}_10") (pintype "bidirectional"))
    )
    (net (code "195") (name "unconnected-(U7-RCLK-Pad12)") (class "Default")
      (node (ref "U7") (pin "12") (pinfunction "RCLK_12") (pintype "bidirectional"))
    )
    (net (code "196") (name "unconnected-(U7-SER_IN-Pad14)") (class "Default")
      (node (ref "U7") (pin "14") (pinfunction "SER_IN_14") (pintype "bidirectional"))
    )
    (net (code "197") (name "unconnected-(U7-SRCLK-Pad11)") (class "Default")
      (node (ref "U7") (pin "11") (pinfunction "SRCLK_11") (pintype "bidirectional"))
    )
    (net (code "198") (name "unconnected-(U7-~{OE}-Pad13)") (class "Default")
      (node (ref "U7") (pin "13") (pinfunction "~{OE}_13") (pintype "bidirectional"))
    )
    (net (code "199") (name "unconnected-(U7-~{QH}-Pad9)") (class "Default")
      (node (ref "U7") (pin "9") (pinfunction "~{QH}_9") (pintype "bidirectional"))
    )
    (net (code "200") (name "unconnected-(U7-~{SPCLR}-Pad10)") (class "Default")
      (node (ref "U7") (pin "10") (pinfunction "~{SPCLR}_10") (pintype "bidirectional"))
    )
    (net (code "201") (name "unconnected-(U9-A-Pad2)") (class "Default")
      (node (ref "U9") (pin "2") (pinfunction "A_2") (pintype "bidirectional"))
    )
  )
)
